# design.net
KiCad netlist of a schematic drawn in Altium Designer
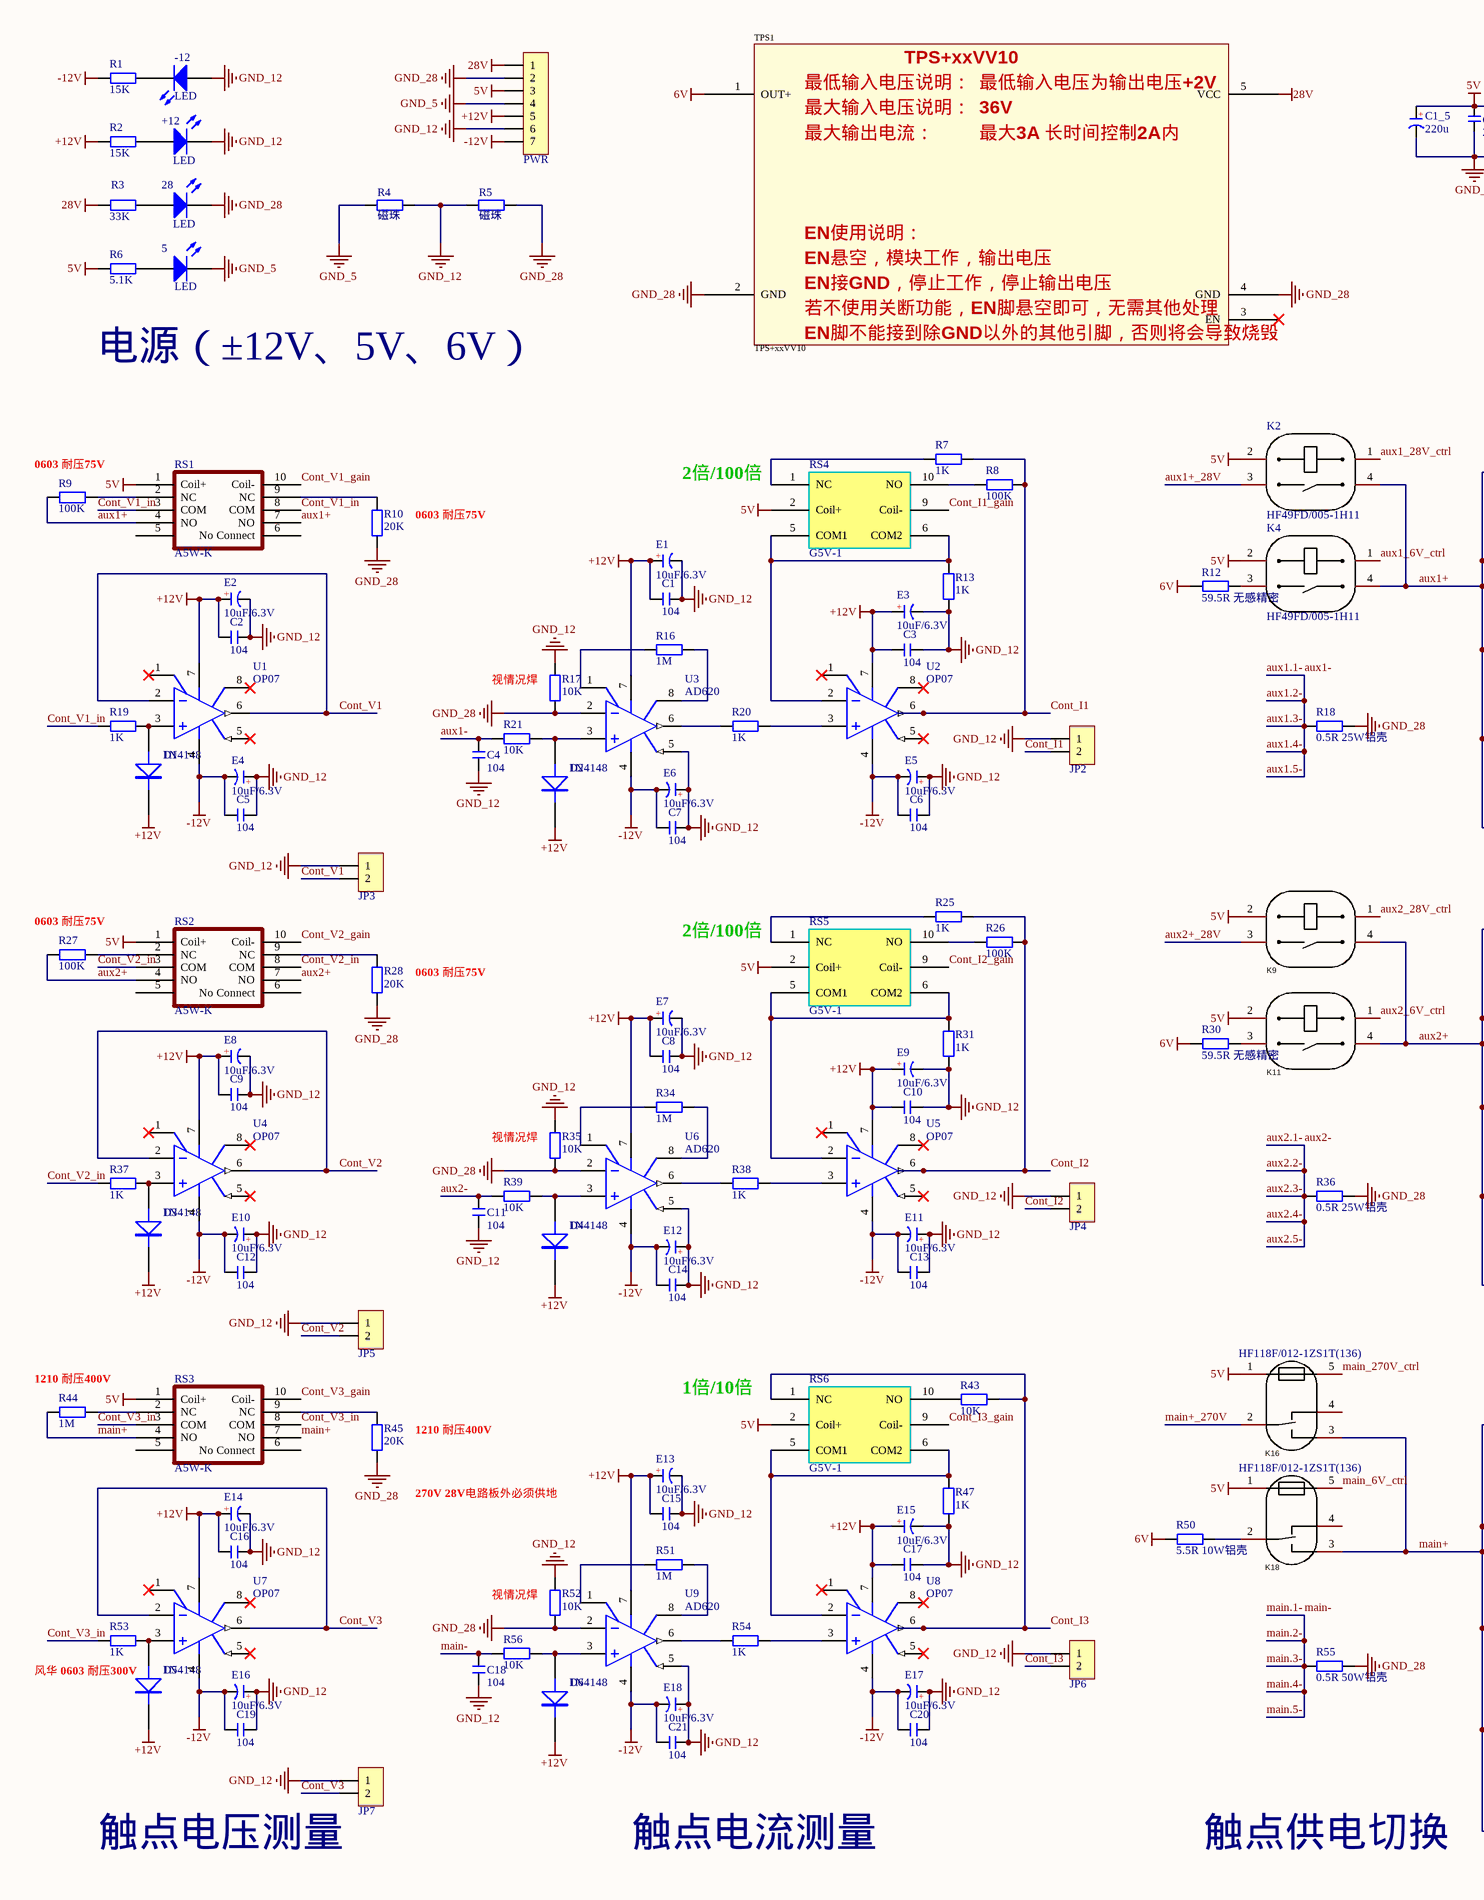
[diagram p0: 测试板.SchDoc, left]
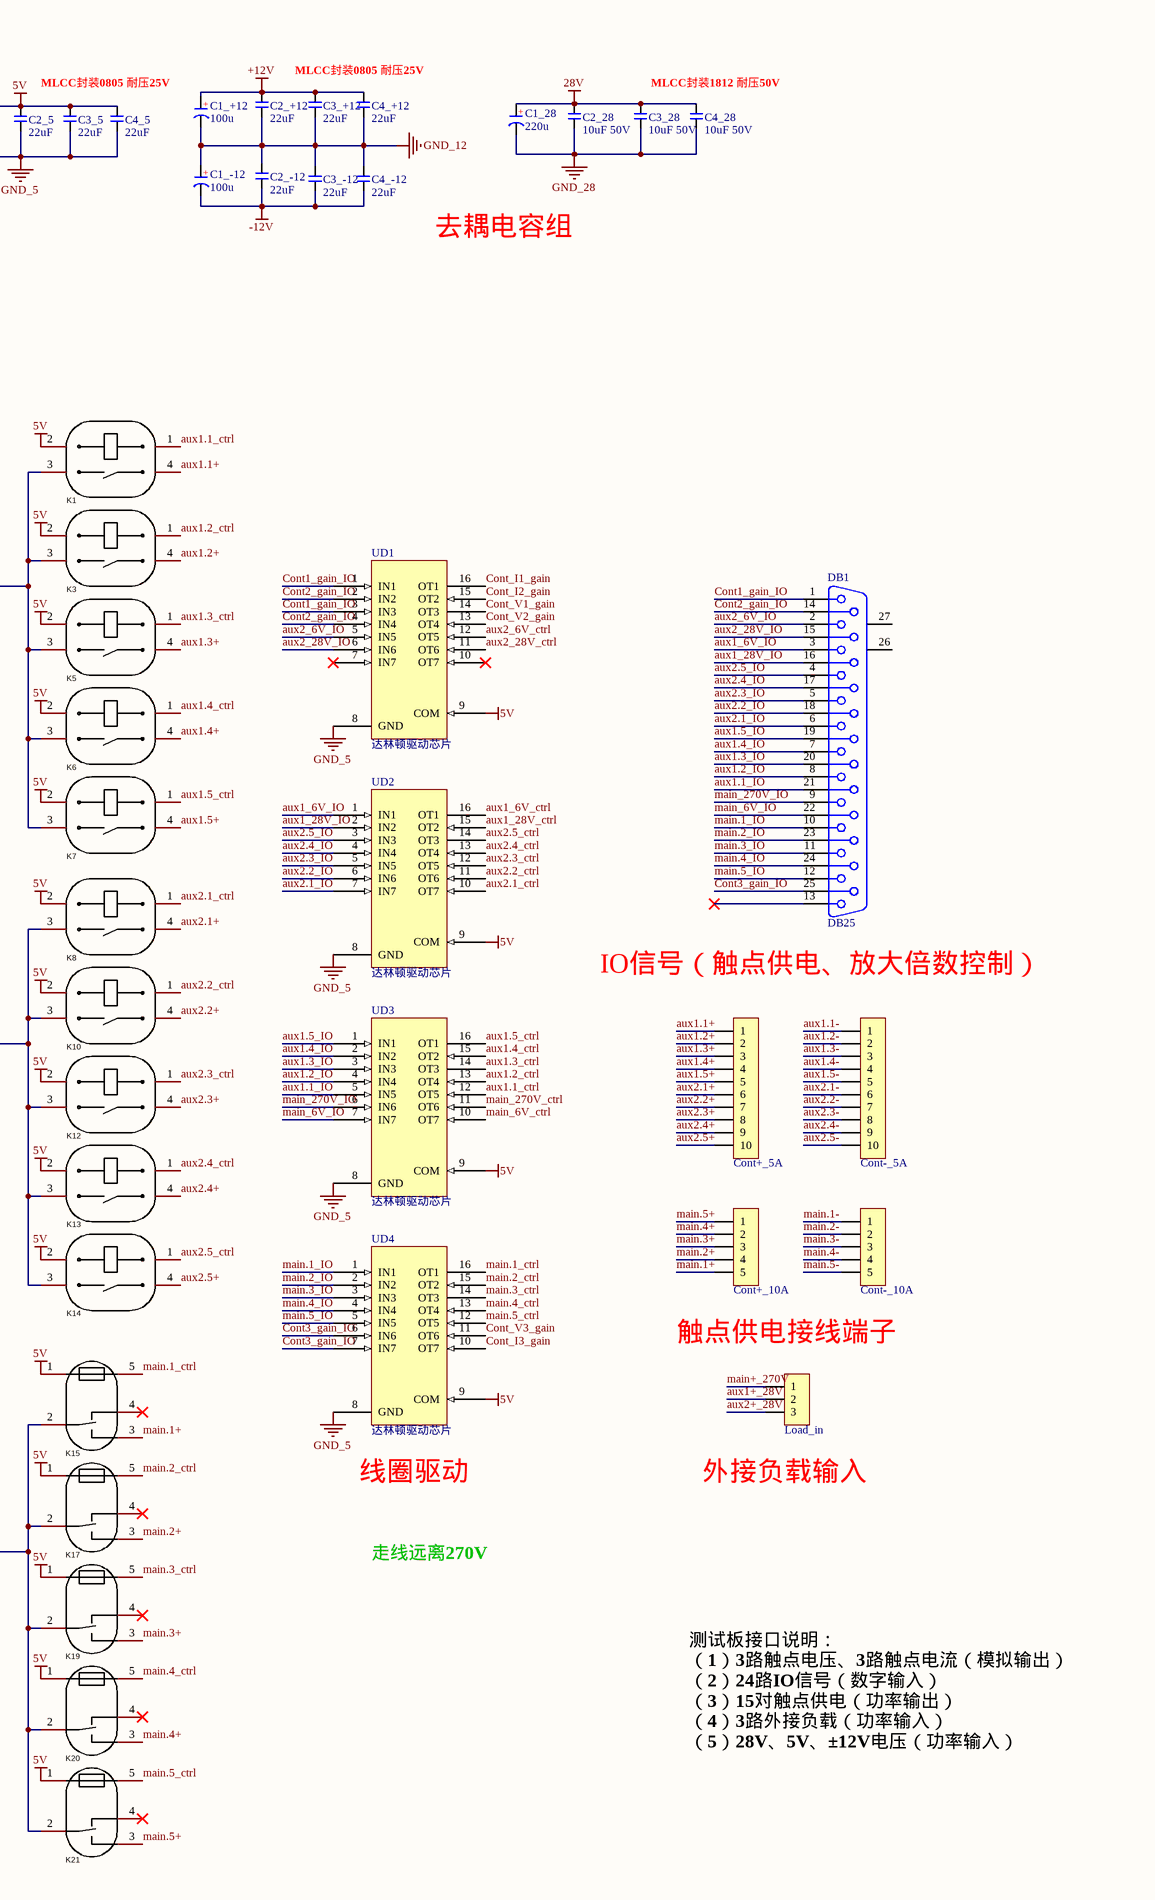
[diagram p1: 测试板.SchDoc, right]

(export (version "E")
  (design (tool "Eeschema 10.0.6"))
  (components
    (comp (ref "+12")
      (value "LED")
      (footprint "LED 0603B")
      (description "Typical BLUE SiC LED")
      (fields (field (name "PUBLISHER") "Altium Limited"))
      (libsource (lib "测控板") (part "LED3"))
    )
    (comp (ref "-12")
      (value "LED")
      (footprint "LED 0603B")
      (description "Typical BLUE SiC LED")
      (fields (field (name "PUBLISHER") "Altium Limited"))
      (libsource (lib "测控板") (part "LED3"))
    )
    (comp (ref "5")
      (value "LED")
      (footprint "LED 0603B")
      (description "Typical BLUE SiC LED")
      (fields (field (name "PUBLISHER") "Altium Limited"))
      (libsource (lib "测控板") (part "LED3"))
    )
    (comp (ref "28")
      (value "LED")
      (footprint "LED 0603B")
      (description "Typical BLUE SiC LED")
      (fields (field (name "PUBLISHER") "Altium Limited"))
      (libsource (lib "测控板") (part "LED3"))
    )
    (comp (ref "C1")
      (value "104")
      (footprint "C 0603_L")
      (description "贴片电容")
      (libsource (lib "0.1 - 电阻-电容-电感") (part "C"))
    )
    (comp (ref "C1_+12")
      (value "100u")
      (footprint "CAP 3.5*8*11.5")
      (description "Tantalum capacitor")
      (libsource (lib "SCHlibrary_of_ZYN") (part "T_CAP"))
    )
    (comp (ref "C1_-12")
      (value "100u")
      (footprint "CAP 3.5*8*11.5")
      (description "Tantalum capacitor")
      (libsource (lib "SCHlibrary_of_ZYN") (part "T_CAP"))
    )
    (comp (ref "C1_5")
      (value "220u")
      (footprint "CAP 3.5*8*11.5")
      (description "Tantalum capacitor")
      (libsource (lib "SCHlibrary_of_ZYN") (part "T_CAP"))
    )
    (comp (ref "C1_28")
      (value "220u")
      (footprint "CAP 3.5*8*11.5")
      (description "Tantalum capacitor")
      (libsource (lib "SCHlibrary_of_ZYN") (part "T_CAP"))
    )
    (comp (ref "C2")
      (value "104")
      (footprint "C 0603_L")
      (description "贴片电容")
      (libsource (lib "0.1 - 电阻-电容-电感") (part "C"))
    )
    (comp (ref "C2_+12")
      (value "xxuF/xxV/Footprint")
      (footprint "C 0805_L")
      (description "CAP MLCC")
      (fields (field (name "SCH NAME") "22uF"))
      (libsource (lib "Basal") (part "CAP MLCC"))
    )
    (comp (ref "C2_-12")
      (value "xxuF/xxV/Footprint")
      (footprint "C 0805_L")
      (description "CAP MLCC")
      (fields (field (name "SCH NAME") "22uF"))
      (libsource (lib "Basal") (part "CAP MLCC"))
    )
    (comp (ref "C2_5")
      (value "xxuF/xxV/Footprint")
      (footprint "C 0805_L")
      (description "CAP MLCC")
      (fields (field (name "SCH NAME") "22uF"))
      (libsource (lib "Basal") (part "CAP MLCC"))
    )
    (comp (ref "C2_28")
      (value "xxuF/xxV/Footprint")
      (footprint "C 1812_L")
      (description "CAP MLCC")
      (fields (field (name "SCH NAME") "10uF 50V"))
      (libsource (lib "Basal") (part "CAP MLCC"))
    )
    (comp (ref "C3")
      (value "104")
      (footprint "C 0603_L")
      (description "贴片电容")
      (libsource (lib "0.1 - 电阻-电容-电感") (part "C"))
    )
    (comp (ref "C3_+12")
      (value "xxuF/xxV/Footprint")
      (footprint "C 0805_L")
      (description "CAP MLCC")
      (fields (field (name "SCH NAME") "22uF"))
      (libsource (lib "Basal") (part "CAP MLCC"))
    )
    (comp (ref "C3_-12")
      (value "xxuF/xxV/Footprint")
      (footprint "C 0805_L")
      (description "CAP MLCC")
      (fields (field (name "SCH NAME") "22uF"))
      (libsource (lib "Basal") (part "CAP MLCC"))
    )
    (comp (ref "C3_5")
      (value "xxuF/xxV/Footprint")
      (footprint "C 0805_L")
      (description "CAP MLCC")
      (fields (field (name "SCH NAME") "22uF"))
      (libsource (lib "Basal") (part "CAP MLCC"))
    )
    (comp (ref "C3_28")
      (value "xxuF/xxV/Footprint")
      (footprint "C 1812_L")
      (description "CAP MLCC")
      (fields (field (name "SCH NAME") "10uF 50V"))
      (libsource (lib "Basal") (part "CAP MLCC"))
    )
    (comp (ref "C4")
      (value "104")
      (footprint "C 0603_L")
      (description "贴片电容")
      (libsource (lib "0.1 - 电阻-电容-电感") (part "C"))
    )
    (comp (ref "C4_+12")
      (value "xxuF/xxV/Footprint")
      (footprint "C 0805_L")
      (description "CAP MLCC")
      (fields (field (name "SCH NAME") "22uF"))
      (libsource (lib "Basal") (part "CAP MLCC"))
    )
    (comp (ref "C4_-12")
      (value "xxuF/xxV/Footprint")
      (footprint "C 0805_L")
      (description "CAP MLCC")
      (fields (field (name "SCH NAME") "22uF"))
      (libsource (lib "Basal") (part "CAP MLCC"))
    )
    (comp (ref "C4_5")
      (value "xxuF/xxV/Footprint")
      (footprint "C 0805_L")
      (description "CAP MLCC")
      (fields (field (name "SCH NAME") "22uF"))
      (libsource (lib "Basal") (part "CAP MLCC"))
    )
    (comp (ref "C4_28")
      (value "xxuF/xxV/Footprint")
      (footprint "C 1812_L")
      (description "CAP MLCC")
      (fields (field (name "SCH NAME") "10uF 50V"))
      (libsource (lib "Basal") (part "CAP MLCC"))
    )
    (comp (ref "C5")
      (value "104")
      (footprint "C 0603_L")
      (description "贴片电容")
      (libsource (lib "0.1 - 电阻-电容-电感") (part "C"))
    )
    (comp (ref "C6")
      (value "104")
      (footprint "C 0603_L")
      (description "贴片电容")
      (libsource (lib "0.1 - 电阻-电容-电感") (part "C"))
    )
    (comp (ref "C7")
      (value "104")
      (footprint "C 0603_L")
      (description "贴片电容")
      (libsource (lib "0.1 - 电阻-电容-电感") (part "C"))
    )
    (comp (ref "C8")
      (value "104")
      (footprint "C 0603_L")
      (description "贴片电容")
      (libsource (lib "0.1 - 电阻-电容-电感") (part "C"))
    )
    (comp (ref "C9")
      (value "104")
      (footprint "C 0603_L")
      (description "贴片电容")
      (libsource (lib "0.1 - 电阻-电容-电感") (part "C"))
    )
    (comp (ref "C10")
      (value "104")
      (footprint "C 0603_L")
      (description "贴片电容")
      (libsource (lib "0.1 - 电阻-电容-电感") (part "C"))
    )
    (comp (ref "C11")
      (value "104")
      (footprint "C 0603_L")
      (description "贴片电容")
      (libsource (lib "0.1 - 电阻-电容-电感") (part "C"))
    )
    (comp (ref "C12")
      (value "104")
      (footprint "C 0603_L")
      (description "贴片电容")
      (libsource (lib "0.1 - 电阻-电容-电感") (part "C"))
    )
    (comp (ref "C13")
      (value "104")
      (footprint "C 0603_L")
      (description "贴片电容")
      (libsource (lib "0.1 - 电阻-电容-电感") (part "C"))
    )
    (comp (ref "C14")
      (value "104")
      (footprint "C 0603_L")
      (description "贴片电容")
      (libsource (lib "0.1 - 电阻-电容-电感") (part "C"))
    )
    (comp (ref "C15")
      (value "104")
      (footprint "C 0603_L")
      (description "贴片电容")
      (libsource (lib "0.1 - 电阻-电容-电感") (part "C"))
    )
    (comp (ref "C16")
      (value "104")
      (footprint "C 0603_L")
      (description "贴片电容")
      (libsource (lib "0.1 - 电阻-电容-电感") (part "C"))
    )
    (comp (ref "C17")
      (value "104")
      (footprint "C 0603_L")
      (description "贴片电容")
      (libsource (lib "0.1 - 电阻-电容-电感") (part "C"))
    )
    (comp (ref "C18")
      (value "104")
      (footprint "C 0603_L")
      (description "贴片电容")
      (libsource (lib "0.1 - 电阻-电容-电感") (part "C"))
    )
    (comp (ref "C19")
      (value "104")
      (footprint "C 0603_L")
      (description "贴片电容")
      (libsource (lib "0.1 - 电阻-电容-电感") (part "C"))
    )
    (comp (ref "C20")
      (value "104")
      (footprint "C 0603_L")
      (description "贴片电容")
      (libsource (lib "0.1 - 电阻-电容-电感") (part "C"))
    )
    (comp (ref "C21")
      (value "104")
      (footprint "C 0603_L")
      (description "贴片电容")
      (libsource (lib "0.1 - 电阻-电容-电感") (part "C"))
    )
    (comp (ref "Cont+_5A")
      (value "HDR-1X10")
      (footprint "HT3.96-WI-10P")
      (description "10P接插件")
      (libsource (lib "5.4 - 接插件-脚距2.54 (100mil) ") (part "Header 10"))
    )
    (comp (ref "Cont+_10A")
      (value "HDR-1X5")
      (footprint "HT3.96-WI-5P")
      (description "5P接插件")
      (fields (field (name "版权归属") "封装库来自淘宝卖家 ID：黄晶宝石"))
      (libsource (lib "5.7 - 接插件-脚距3.96") (part "Header 5"))
    )
    (comp (ref "Cont-_5A")
      (value "HDR-1X10")
      (footprint "HT3.96-WI-10P")
      (description "10P接插件")
      (libsource (lib "5.4 - 接插件-脚距2.54 (100mil) ") (part "Header 10"))
    )
    (comp (ref "Cont-_10A")
      (value "HDR-1X5")
      (footprint "HT3.96-WI-5P")
      (description "5P接插件")
      (fields (field (name "版权归属") "封装库来自淘宝卖家 ID：黄晶宝石"))
      (libsource (lib "5.7 - 接插件-脚距3.96") (part "Header 5"))
    )
    (comp (ref "D1")
      (value "1N4148")
      (footprint "SOD-323")
      (description "Diode")
      (libsource (lib "测控板") (part "DIODE"))
    )
    (comp (ref "D2")
      (value "1N4148")
      (footprint "SOD-323")
      (description "Diode")
      (libsource (lib "测控板") (part "DIODE"))
    )
    (comp (ref "D3")
      (value "1N4148")
      (footprint "SOD-323")
      (description "Diode")
      (libsource (lib "测控板") (part "DIODE"))
    )
    (comp (ref "D4")
      (value "1N4148")
      (footprint "SOD-323")
      (description "Diode")
      (libsource (lib "测控板") (part "DIODE"))
    )
    (comp (ref "D5")
      (value "1N4148")
      (footprint "SOD-323")
      (description "Diode")
      (libsource (lib "测控板") (part "DIODE"))
    )
    (comp (ref "D6")
      (value "1N4148")
      (footprint "SOD-323")
      (description "Diode")
      (libsource (lib "测控板") (part "DIODE"))
    )
    (comp (ref "DB1")
      (value "DB25")
      (footprint "DB25")
      (description "Receptacle Assembly, 25 Position, Right Angle")
      (fields (field (name "PUBLISHER") "Altium Limited"))
      (libsource (lib "DDY library SCH") (part "D Connector 25"))
    )
    (comp (ref "E1")
      (value "10uF/6.3V")
      (footprint "CD B(3528)")
      (description "贴片钽电容")
      (libsource (lib "0.1 - 电阻-电容-电感") (part "CT"))
    )
    (comp (ref "E2")
      (value "10uF/6.3V")
      (footprint "CD B(3528)")
      (description "贴片钽电容")
      (libsource (lib "0.1 - 电阻-电容-电感") (part "CT"))
    )
    (comp (ref "E3")
      (value "10uF/6.3V")
      (footprint "CD B(3528)")
      (description "贴片钽电容")
      (libsource (lib "0.1 - 电阻-电容-电感") (part "CT"))
    )
    (comp (ref "E4")
      (value "10uF/6.3V")
      (footprint "CD B(3528)")
      (description "贴片钽电容")
      (libsource (lib "0.1 - 电阻-电容-电感") (part "CT"))
    )
    (comp (ref "E5")
      (value "10uF/6.3V")
      (footprint "CD B(3528)")
      (description "贴片钽电容")
      (libsource (lib "0.1 - 电阻-电容-电感") (part "CT"))
    )
    (comp (ref "E6")
      (value "10uF/6.3V")
      (footprint "CD B(3528)")
      (description "贴片钽电容")
      (libsource (lib "0.1 - 电阻-电容-电感") (part "CT"))
    )
    (comp (ref "E7")
      (value "10uF/6.3V")
      (footprint "CD B(3528)")
      (description "贴片钽电容")
      (libsource (lib "0.1 - 电阻-电容-电感") (part "CT"))
    )
    (comp (ref "E8")
      (value "10uF/6.3V")
      (footprint "CD B(3528)")
      (description "贴片钽电容")
      (libsource (lib "0.1 - 电阻-电容-电感") (part "CT"))
    )
    (comp (ref "E9")
      (value "10uF/6.3V")
      (footprint "CD B(3528)")
      (description "贴片钽电容")
      (libsource (lib "0.1 - 电阻-电容-电感") (part "CT"))
    )
    (comp (ref "E10")
      (value "10uF/6.3V")
      (footprint "CD B(3528)")
      (description "贴片钽电容")
      (libsource (lib "0.1 - 电阻-电容-电感") (part "CT"))
    )
    (comp (ref "E11")
      (value "10uF/6.3V")
      (footprint "CD B(3528)")
      (description "贴片钽电容")
      (libsource (lib "0.1 - 电阻-电容-电感") (part "CT"))
    )
    (comp (ref "E12")
      (value "10uF/6.3V")
      (footprint "CD B(3528)")
      (description "贴片钽电容")
      (libsource (lib "0.1 - 电阻-电容-电感") (part "CT"))
    )
    (comp (ref "E13")
      (value "10uF/6.3V")
      (footprint "CD B(3528)")
      (description "贴片钽电容")
      (libsource (lib "0.1 - 电阻-电容-电感") (part "CT"))
    )
    (comp (ref "E14")
      (value "10uF/6.3V")
      (footprint "CD B(3528)")
      (description "贴片钽电容")
      (libsource (lib "0.1 - 电阻-电容-电感") (part "CT"))
    )
    (comp (ref "E15")
      (value "10uF/6.3V")
      (footprint "CD B(3528)")
      (description "贴片钽电容")
      (libsource (lib "0.1 - 电阻-电容-电感") (part "CT"))
    )
    (comp (ref "E16")
      (value "10uF/6.3V")
      (footprint "CD B(3528)")
      (description "贴片钽电容")
      (libsource (lib "0.1 - 电阻-电容-电感") (part "CT"))
    )
    (comp (ref "E17")
      (value "10uF/6.3V")
      (footprint "CD B(3528)")
      (description "贴片钽电容")
      (libsource (lib "0.1 - 电阻-电容-电感") (part "CT"))
    )
    (comp (ref "E18")
      (value "10uF/6.3V")
      (footprint "CD B(3528)")
      (description "贴片钽电容")
      (libsource (lib "0.1 - 电阻-电容-电感") (part "CT"))
    )
    (comp (ref "JP2")
      (value "HDR-1X2")
      (footprint "KF2EDGK-2.54-WI-2P")
      (description "2P接插件")
      (fields (field (name "版权归属") "封装库来自淘宝 ID：黄晶宝石"))
      (libsource (lib "5.4 - 接插件-脚距2.54 (100mil) ") (part "Header 2"))
    )
    (comp (ref "JP3")
      (value "HDR-1X2")
      (footprint "KF2EDGK-2.54-WI-2P")
      (description "2P接插件")
      (fields (field (name "版权归属") "封装库来自淘宝 ID：黄晶宝石"))
      (libsource (lib "5.4 - 接插件-脚距2.54 (100mil) ") (part "Header 2"))
    )
    (comp (ref "JP4")
      (value "HDR-1X2")
      (footprint "KF2EDGK-2.54-WI-2P")
      (description "2P接插件")
      (fields (field (name "版权归属") "封装库来自淘宝 ID：黄晶宝石"))
      (libsource (lib "5.4 - 接插件-脚距2.54 (100mil) ") (part "Header 2"))
    )
    (comp (ref "JP5")
      (value "HDR-1X2")
      (footprint "KF2EDGK-2.54-WI-2P")
      (description "2P接插件")
      (fields (field (name "版权归属") "封装库来自淘宝 ID：黄晶宝石"))
      (libsource (lib "5.4 - 接插件-脚距2.54 (100mil) ") (part "Header 2"))
    )
    (comp (ref "JP6")
      (value "HDR-1X2")
      (footprint "KF2EDGK-2.54-WI-2P")
      (description "2P接插件")
      (fields (field (name "版权归属") "封装库来自淘宝 ID：黄晶宝石"))
      (libsource (lib "5.4 - 接插件-脚距2.54 (100mil) ") (part "Header 2"))
    )
    (comp (ref "JP7")
      (value "HDR-1X2")
      (footprint "KF2EDGK-2.54-WI-2P")
      (description "2P接插件")
      (fields (field (name "版权归属") "封装库来自淘宝 ID：黄晶宝石"))
      (libsource (lib "5.4 - 接插件-脚距2.54 (100mil) ") (part "Header 2"))
    )
    (comp (ref "K1")
      (value "HF49FD/005-1H11")
      (footprint "HF49FD-1H11")
      (fields (field (name "MANUFACTURER") "HF(宏发)"))
      (libsource (lib "HF49FD_005-1H11") (part "HF49FD/005-1H11"))
    )
    (comp (ref "K2")
      (value "HF49FD/005-1H11")
      (footprint "HF49FD-1H11")
      (fields (field (name "MANUFACTURER") "HF(宏发)"))
      (libsource (lib "HF49FD_005-1H11") (part "HF49FD/005-1H11"))
    )
    (comp (ref "K3")
      (value "HF49FD/005-1H11")
      (footprint "HF49FD-1H11")
      (fields (field (name "MANUFACTURER") "HF(宏发)"))
      (libsource (lib "HF49FD_005-1H11") (part "HF49FD/005-1H11"))
    )
    (comp (ref "K4")
      (value "HF49FD/005-1H11")
      (footprint "HF49FD-1H11")
      (fields (field (name "MANUFACTURER") "HF(宏发)"))
      (libsource (lib "HF49FD_005-1H11") (part "HF49FD/005-1H11"))
    )
    (comp (ref "K5")
      (value "HF49FD/005-1H11")
      (footprint "HF49FD-1H11")
      (fields (field (name "MANUFACTURER") "HF(宏发)"))
      (libsource (lib "HF49FD_005-1H11") (part "HF49FD/005-1H11"))
    )
    (comp (ref "K6")
      (value "HF49FD/005-1H11")
      (footprint "HF49FD-1H11")
      (fields (field (name "MANUFACTURER") "HF(宏发)"))
      (libsource (lib "HF49FD_005-1H11") (part "HF49FD/005-1H11"))
    )
    (comp (ref "K7")
      (value "HF49FD/005-1H11")
      (footprint "HF49FD-1H11")
      (fields (field (name "MANUFACTURER") "HF(宏发)"))
      (libsource (lib "HF49FD_005-1H11") (part "HF49FD/005-1H11"))
    )
    (comp (ref "K8")
      (value "HF49FD/005-1H11")
      (footprint "HF49FD-1H11")
      (fields (field (name "MANUFACTURER") "HF(宏发)"))
      (libsource (lib "HF49FD_005-1H11") (part "HF49FD/005-1H11"))
    )
    (comp (ref "K9")
      (value "HF49FD/005-1H11")
      (footprint "HF49FD-1H11")
      (fields (field (name "MANUFACTURER") "HF(宏发)"))
      (libsource (lib "HF49FD_005-1H11") (part "HF49FD/005-1H11"))
    )
    (comp (ref "K10")
      (value "HF49FD/005-1H11")
      (footprint "HF49FD-1H11")
      (fields (field (name "MANUFACTURER") "HF(宏发)"))
      (libsource (lib "HF49FD_005-1H11") (part "HF49FD/005-1H11"))
    )
    (comp (ref "K11")
      (value "HF49FD/005-1H11")
      (footprint "HF49FD-1H11")
      (fields (field (name "MANUFACTURER") "HF(宏发)"))
      (libsource (lib "HF49FD_005-1H11") (part "HF49FD/005-1H11"))
    )
    (comp (ref "K12")
      (value "HF49FD/005-1H11")
      (footprint "HF49FD-1H11")
      (fields (field (name "MANUFACTURER") "HF(宏发)"))
      (libsource (lib "HF49FD_005-1H11") (part "HF49FD/005-1H11"))
    )
    (comp (ref "K13")
      (value "HF49FD/005-1H11")
      (footprint "HF49FD-1H11")
      (fields (field (name "MANUFACTURER") "HF(宏发)"))
      (libsource (lib "HF49FD_005-1H11") (part "HF49FD/005-1H11"))
    )
    (comp (ref "K14")
      (value "HF49FD/005-1H11")
      (footprint "HF49FD-1H11")
      (fields (field (name "MANUFACTURER") "HF(宏发)"))
      (libsource (lib "HF49FD_005-1H11") (part "HF49FD/005-1H11"))
    )
    (comp (ref "K15")
      (value "HF118F/012-1ZS1T(136)")
      (footprint "RELAY-TH_HF118F-X-1ZX1X-XXX")
      (fields (field (name "MANUFACTURER") "HF(宏发)"))
      (libsource (lib "HF118F_012-1ZS1T") (part "HF118F/012-1ZS1T(136)"))
    )
    (comp (ref "K16")
      (value "HF118F/012-1ZS1T(136)")
      (footprint "RELAY-TH_HF118F-X-1ZX1X-XXX")
      (fields (field (name "MANUFACTURER") "HF(宏发)"))
      (libsource (lib "HF118F_012-1ZS1T") (part "HF118F/012-1ZS1T(136)"))
    )
    (comp (ref "K17")
      (value "HF118F/012-1ZS1T(136)")
      (footprint "RELAY-TH_HF118F-X-1ZX1X-XXX")
      (fields (field (name "MANUFACTURER") "HF(宏发)"))
      (libsource (lib "HF118F_012-1ZS1T") (part "HF118F/012-1ZS1T(136)"))
    )
    (comp (ref "K18")
      (value "HF118F/012-1ZS1T(136)")
      (footprint "RELAY-TH_HF118F-X-1ZX1X-XXX")
      (fields (field (name "MANUFACTURER") "HF(宏发)"))
      (libsource (lib "HF118F_012-1ZS1T") (part "HF118F/012-1ZS1T(136)"))
    )
    (comp (ref "K19")
      (value "HF118F/012-1ZS1T(136)")
      (footprint "RELAY-TH_HF118F-X-1ZX1X-XXX")
      (fields (field (name "MANUFACTURER") "HF(宏发)"))
      (libsource (lib "HF118F_012-1ZS1T") (part "HF118F/012-1ZS1T(136)"))
    )
    (comp (ref "K20")
      (value "HF118F/012-1ZS1T(136)")
      (footprint "RELAY-TH_HF118F-X-1ZX1X-XXX")
      (fields (field (name "MANUFACTURER") "HF(宏发)"))
      (libsource (lib "HF118F_012-1ZS1T") (part "HF118F/012-1ZS1T(136)"))
    )
    (comp (ref "K21")
      (value "HF118F/012-1ZS1T(136)")
      (footprint "RELAY-TH_HF118F-X-1ZX1X-XXX")
      (fields (field (name "MANUFACTURER") "HF(宏发)"))
      (libsource (lib "HF118F_012-1ZS1T") (part "HF118F/012-1ZS1T(136)"))
    )
    (comp (ref "Load_in")
      (value "HDR-1X3")
      (footprint "HT3.96-WI-3P")
      (description "3P接插件")
      (fields (field (name "版权归属") "封装库来自淘宝卖家 ID：黄晶宝石"))
      (libsource (lib "5.7 - 接插件-脚距3.96") (part "Header 3"))
    )
    (comp (ref "PWR")
      (value "HDR-1X7")
      (footprint "HT3.96-WI-7P")
      (description "7P接插件")
      (fields (field (name "版权归属") "封装库来自淘宝卖家 ID：黄晶宝石"))
      (libsource (lib "6.1 - 接插件-脚距5.08 (200mil) ") (part "Header 7"))
    )
    (comp (ref "R1")
      (value "15K")
      (footprint "R 0603_L")
      (description "贴片电阻")
      (fields (field (name "版权归属") "来自淘宝 ID：黄晶宝石"))
      (libsource (lib "0.1 - 电阻-电容-电感") (part "R"))
    )
    (comp (ref "R2")
      (value "15K")
      (footprint "R 0603_L")
      (description "贴片电阻")
      (fields (field (name "版权归属") "来自淘宝 ID：黄晶宝石"))
      (libsource (lib "0.1 - 电阻-电容-电感") (part "R"))
    )
    (comp (ref "R3")
      (value "33K")
      (footprint "R 0603_L")
      (description "贴片电阻")
      (fields (field (name "版权归属") "来自淘宝 ID：黄晶宝石"))
      (libsource (lib "0.1 - 电阻-电容-电感") (part "R"))
    )
    (comp (ref "R4")
      (value "磁珠")
      (footprint "AXIAL0.4-1/4W")
      (description "Resistor")
      (fields (field (name "PUBLISHER") "Altium Limited"))
      (libsource (lib "Miscellaneous Devices") (part "Res2"))
    )
    (comp (ref "R5")
      (value "磁珠")
      (footprint "AXIAL0.4-1/4W")
      (description "Resistor")
      (fields (field (name "PUBLISHER") "Altium Limited"))
      (libsource (lib "Miscellaneous Devices") (part "Res2"))
    )
    (comp (ref "R6")
      (value "5.1K")
      (footprint "R 0603_L")
      (description "贴片电阻")
      (fields (field (name "版权归属") "来自淘宝 ID：黄晶宝石"))
      (libsource (lib "0.1 - 电阻-电容-电感") (part "R"))
    )
    (comp (ref "R7")
      (value "1K")
      (footprint "R 0603_L")
      (description "贴片电阻")
      (fields (field (name "版权归属") "来自淘宝 ID：黄晶宝石"))
      (libsource (lib "0.1 - 电阻-电容-电感") (part "R"))
    )
    (comp (ref "R8")
      (value "100K")
      (footprint "R 0603_L")
      (description "贴片电阻")
      (fields (field (name "版权归属") "来自淘宝 ID：黄晶宝石"))
      (libsource (lib "0.1 - 电阻-电容-电感") (part "R"))
    )
    (comp (ref "R9")
      (value "100K")
      (footprint "R 0603_L")
      (description "贴片电阻")
      (fields (field (name "版权归属") "来自淘宝 ID：黄晶宝石"))
      (libsource (lib "0.1 - 电阻-电容-电感") (part "R"))
    )
    (comp (ref "R10")
      (value "20K")
      (footprint "R 0603_L")
      (description "贴片电阻")
      (fields (field (name "版权归属") "来自淘宝 ID：黄晶宝石"))
      (libsource (lib "0.1 - 电阻-电容-电感") (part "R"))
    )
    (comp (ref "R12")
      (value "59.5R 无感精密")
      (footprint "无感精密电阻3W")
      (description "贴片电阻")
      (fields (field (name "版权归属") "来自淘宝 ID：黄晶宝石"))
      (libsource (lib "0.1 - 电阻-电容-电感") (part "R"))
    )
    (comp (ref "R13")
      (value "1K")
      (footprint "R 0603_L")
      (description "贴片电阻")
      (fields (field (name "版权归属") "来自淘宝 ID：黄晶宝石"))
      (libsource (lib "0.1 - 电阻-电容-电感") (part "R"))
    )
    (comp (ref "R16")
      (value "1M")
      (footprint "R 0603_L")
      (description "贴片电阻")
      (fields (field (name "版权归属") "来自淘宝 ID：黄晶宝石"))
      (libsource (lib "0.1 - 电阻-电容-电感") (part "R"))
    )
    (comp (ref "R17")
      (value "10K")
      (footprint "R 0603_L")
      (description "贴片电阻")
      (fields (field (name "版权归属") "来自淘宝 ID：黄晶宝石"))
      (libsource (lib "0.1 - 电阻-电容-电感") (part "R"))
    )
    (comp (ref "R18")
      (value "0.5R 25W铝壳")
      (footprint "黄金铝壳1R25W")
      (description "贴片电阻")
      (fields (field (name "版权归属") "来自淘宝 ID：黄晶宝石"))
      (libsource (lib "0.1 - 电阻-电容-电感") (part "R"))
    )
    (comp (ref "R19")
      (value "1K")
      (footprint "R 0603_L")
      (description "贴片电阻")
      (fields (field (name "版权归属") "来自淘宝 ID：黄晶宝石"))
      (libsource (lib "0.1 - 电阻-电容-电感") (part "R"))
    )
    (comp (ref "R20")
      (value "1K")
      (footprint "R 0603_L")
      (description "贴片电阻")
      (fields (field (name "版权归属") "来自淘宝 ID：黄晶宝石"))
      (libsource (lib "0.1 - 电阻-电容-电感") (part "R"))
    )
    (comp (ref "R21")
      (value "10K")
      (footprint "R 0603_L")
      (description "贴片电阻")
      (fields (field (name "版权归属") "来自淘宝 ID：黄晶宝石"))
      (libsource (lib "0.1 - 电阻-电容-电感") (part "R"))
    )
    (comp (ref "R25")
      (value "1K")
      (footprint "R 0603_L")
      (description "贴片电阻")
      (fields (field (name "版权归属") "来自淘宝 ID：黄晶宝石"))
      (libsource (lib "0.1 - 电阻-电容-电感") (part "R"))
    )
    (comp (ref "R26")
      (value "100K")
      (footprint "R 0603_L")
      (description "贴片电阻")
      (fields (field (name "版权归属") "来自淘宝 ID：黄晶宝石"))
      (libsource (lib "0.1 - 电阻-电容-电感") (part "R"))
    )
    (comp (ref "R27")
      (value "100K")
      (footprint "R 0603_L")
      (description "贴片电阻")
      (fields (field (name "版权归属") "来自淘宝 ID：黄晶宝石"))
      (libsource (lib "0.1 - 电阻-电容-电感") (part "R"))
    )
    (comp (ref "R28")
      (value "20K")
      (footprint "R 0603_L")
      (description "贴片电阻")
      (fields (field (name "版权归属") "来自淘宝 ID：黄晶宝石"))
      (libsource (lib "0.1 - 电阻-电容-电感") (part "R"))
    )
    (comp (ref "R30")
      (value "59.5R 无感精密")
      (footprint "无感精密电阻3W")
      (description "贴片电阻")
      (fields (field (name "版权归属") "来自淘宝 ID：黄晶宝石"))
      (libsource (lib "0.1 - 电阻-电容-电感") (part "R"))
    )
    (comp (ref "R31")
      (value "1K")
      (footprint "R 0603_L")
      (description "贴片电阻")
      (fields (field (name "版权归属") "来自淘宝 ID：黄晶宝石"))
      (libsource (lib "0.1 - 电阻-电容-电感") (part "R"))
    )
    (comp (ref "R34")
      (value "1M")
      (footprint "R 0603_L")
      (description "贴片电阻")
      (fields (field (name "版权归属") "来自淘宝 ID：黄晶宝石"))
      (libsource (lib "0.1 - 电阻-电容-电感") (part "R"))
    )
    (comp (ref "R35")
      (value "10K")
      (footprint "R 0603_L")
      (description "贴片电阻")
      (fields (field (name "版权归属") "来自淘宝 ID：黄晶宝石"))
      (libsource (lib "0.1 - 电阻-电容-电感") (part "R"))
    )
    (comp (ref "R36")
      (value "0.5R 25W铝壳")
      (footprint "黄金铝壳1R25W")
      (description "贴片电阻")
      (fields (field (name "版权归属") "来自淘宝 ID：黄晶宝石"))
      (libsource (lib "0.1 - 电阻-电容-电感") (part "R"))
    )
    (comp (ref "R37")
      (value "1K")
      (footprint "R 0603_L")
      (description "贴片电阻")
      (fields (field (name "版权归属") "来自淘宝 ID：黄晶宝石"))
      (libsource (lib "0.1 - 电阻-电容-电感") (part "R"))
    )
    (comp (ref "R38")
      (value "1K")
      (footprint "R 0603_L")
      (description "贴片电阻")
      (fields (field (name "版权归属") "来自淘宝 ID：黄晶宝石"))
      (libsource (lib "0.1 - 电阻-电容-电感") (part "R"))
    )
    (comp (ref "R39")
      (value "10K")
      (footprint "R 0603_L")
      (description "贴片电阻")
      (fields (field (name "版权归属") "来自淘宝 ID：黄晶宝石"))
      (libsource (lib "0.1 - 电阻-电容-电感") (part "R"))
    )
    (comp (ref "R43")
      (value "10K")
      (footprint "R 0603_L")
      (description "贴片电阻")
      (fields (field (name "版权归属") "来自淘宝 ID：黄晶宝石"))
      (libsource (lib "0.1 - 电阻-电容-电感") (part "R"))
    )
    (comp (ref "R44")
      (value "1M")
      (footprint "R 2010_L")
      (description "贴片电阻")
      (fields (field (name "版权归属") "来自淘宝 ID：黄晶宝石"))
      (libsource (lib "0.1 - 电阻-电容-电感") (part "R"))
    )
    (comp (ref "R45")
      (value "20K")
      (footprint "R 2010_L")
      (description "贴片电阻")
      (fields (field (name "版权归属") "来自淘宝 ID：黄晶宝石"))
      (libsource (lib "0.1 - 电阻-电容-电感") (part "R"))
    )
    (comp (ref "R47")
      (value "1K")
      (footprint "R 0603_L")
      (description "贴片电阻")
      (fields (field (name "版权归属") "来自淘宝 ID：黄晶宝石"))
      (libsource (lib "0.1 - 电阻-电容-电感") (part "R"))
    )
    (comp (ref "R50")
      (value "5.5R 10W铝壳")
      (footprint "RX24-10W")
      (description "贴片电阻")
      (fields (field (name "版权归属") "来自淘宝 ID：黄晶宝石"))
      (libsource (lib "0.1 - 电阻-电容-电感") (part "R"))
    )
    (comp (ref "R51")
      (value "1M")
      (footprint "R 0603_L")
      (description "贴片电阻")
      (fields (field (name "版权归属") "来自淘宝 ID：黄晶宝石"))
      (libsource (lib "0.1 - 电阻-电容-电感") (part "R"))
    )
    (comp (ref "R52")
      (value "10K")
      (footprint "R 0603_L")
      (description "贴片电阻")
      (fields (field (name "版权归属") "来自淘宝 ID：黄晶宝石"))
      (libsource (lib "0.1 - 电阻-电容-电感") (part "R"))
    )
    (comp (ref "R53")
      (value "1K")
      (footprint "R 0603_L")
      (description "贴片电阻")
      (fields (field (name "版权归属") "来自淘宝 ID：黄晶宝石"))
      (libsource (lib "0.1 - 电阻-电容-电感") (part "R"))
    )
    (comp (ref "R54")
      (value "1K")
      (footprint "R 0603_L")
      (description "贴片电阻")
      (fields (field (name "版权归属") "来自淘宝 ID：黄晶宝石"))
      (libsource (lib "0.1 - 电阻-电容-电感") (part "R"))
    )
    (comp (ref "R55")
      (value "0.5R 50W铝壳")
      (footprint "黄金铝壳0.5R50W")
      (description "贴片电阻")
      (fields (field (name "版权归属") "来自淘宝 ID：黄晶宝石"))
      (libsource (lib "0.1 - 电阻-电容-电感") (part "R"))
    )
    (comp (ref "R56")
      (value "10K")
      (footprint "R 0603_L")
      (description "贴片电阻")
      (fields (field (name "版权归属") "来自淘宝 ID：黄晶宝石"))
      (libsource (lib "0.1 - 电阻-电容-电感") (part "R"))
    )
    (comp (ref "RS1") (value "A5W-K") (footprint "NewA5W_K") (libsource (lib "测控板") (part "Relay")))
    (comp (ref "RS2") (value "A5W-K") (footprint "NewA5W_K") (libsource (lib "测控板") (part "Relay")))
    (comp (ref "RS3") (value "A5W-K") (footprint "NewA5W_K") (libsource (lib "测控板") (part "Relay")))
    (comp (ref "RS4") (value "G5V-1") (footprint "G5V-1") (libsource (lib "G5V-1") (part "G5V-1")))
    (comp (ref "RS5") (value "G5V-1") (footprint "G5V-1") (libsource (lib "G5V-1") (part "G5V-1")))
    (comp (ref "RS6") (value "G5V-1") (footprint "G5V-1") (libsource (lib "G5V-1") (part "G5V-1")))
    (comp (ref "TPS1")
      (value "TPS+xxVV10")
      (footprint "TPS+xxVV10模块贴片封装")
      (libsource (lib "【TPS+xxVV10】模块封装资料") (part "TPS+xxVV10"))
    )
    (comp (ref "U1")
      (value "OP07")
      (footprint "SOP8")
      (description "Precision Instrumentation Amplifier")
      (libsource (lib "测控板") (part "AD620AR (8)"))
    )
    (comp (ref "U2")
      (value "OP07")
      (footprint "SOP8")
      (description "Precision Instrumentation Amplifier")
      (libsource (lib "测控板") (part "AD620AR (8)"))
    )
    (comp (ref "U3")
      (value "AD620")
      (footprint "SOP8")
      (description "Precision Instrumentation Amplifier")
      (libsource (lib "测控板") (part "AD620AR (8)"))
    )
    (comp (ref "U4")
      (value "OP07")
      (footprint "SOP8")
      (description "Precision Instrumentation Amplifier")
      (libsource (lib "测控板") (part "AD620AR (8)"))
    )
    (comp (ref "U5")
      (value "OP07")
      (footprint "SOP8")
      (description "Precision Instrumentation Amplifier")
      (libsource (lib "测控板") (part "AD620AR (8)"))
    )
    (comp (ref "U6")
      (value "AD620")
      (footprint "SOP8")
      (description "Precision Instrumentation Amplifier")
      (libsource (lib "测控板") (part "AD620AR (8)"))
    )
    (comp (ref "U7")
      (value "OP07")
      (footprint "SOP8")
      (description "Precision Instrumentation Amplifier")
      (libsource (lib "测控板") (part "AD620AR (8)"))
    )
    (comp (ref "U8")
      (value "OP07")
      (footprint "SOP8")
      (description "Precision Instrumentation Amplifier")
      (libsource (lib "测控板") (part "AD620AR (8)"))
    )
    (comp (ref "U9")
      (value "AD620")
      (footprint "SOP8")
      (description "Precision Instrumentation Amplifier")
      (libsource (lib "测控板") (part "AD620AR (8)"))
    )
    (comp (ref "UD1") (value "达林顿驱动芯片") (footprint "SOP16") (libsource (lib "1.0 - 常见芯片") (part "ULN2003")))
    (comp (ref "UD2") (value "达林顿驱动芯片") (footprint "SOP16") (libsource (lib "1.0 - 常见芯片") (part "ULN2003")))
    (comp (ref "UD3") (value "达林顿驱动芯片") (footprint "SOP16") (libsource (lib "1.0 - 常见芯片") (part "ULN2003")))
    (comp (ref "UD4") (value "达林顿驱动芯片") (footprint "SOP16") (libsource (lib "1.0 - 常见芯片") (part "ULN2003")))
  )
  (nets
    (net (code "1") (name "+12V") (class "Default")
      (node (ref "C1") (pin "1") (pinfunction "1_1") (pintype "passive"))
      (node (ref "C10") (pin "1") (pinfunction "1_1") (pintype "passive"))
      (node (ref "C15") (pin "1") (pinfunction "1_1") (pintype "passive"))
      (node (ref "C16") (pin "1") (pinfunction "1_1") (pintype "passive"))
      (node (ref "C17") (pin "1") (pinfunction "1_1") (pintype "passive"))
      (node (ref "C1_+12") (pin "1") (pinfunction "A_1") (pintype "passive"))
      (node (ref "C2") (pin "1") (pinfunction "1_1") (pintype "passive"))
      (node (ref "C2_+12") (pin "1") (pintype "passive"))
      (node (ref "C3") (pin "1") (pinfunction "1_1") (pintype "passive"))
      (node (ref "C3_+12") (pin "1") (pintype "passive"))
      (node (ref "C4_+12") (pin "1") (pintype "passive"))
      (node (ref "C8") (pin "1") (pinfunction "1_1") (pintype "passive"))
      (node (ref "C9") (pin "1") (pinfunction "1_1") (pintype "passive"))
      (node (ref "D1") (pin "2") (pinfunction "K_2") (pintype "passive"))
      (node (ref "D2") (pin "2") (pinfunction "K_2") (pintype "passive"))
      (node (ref "D3") (pin "2") (pinfunction "K_2") (pintype "passive"))
      (node (ref "D4") (pin "2") (pinfunction "K_2") (pintype "passive"))
      (node (ref "D5") (pin "2") (pinfunction "K_2") (pintype "passive"))
      (node (ref "D6") (pin "2") (pinfunction "K_2") (pintype "passive"))
      (node (ref "E1") (pin "1") (pinfunction "A_1") (pintype "passive"))
      (node (ref "E13") (pin "1") (pinfunction "A_1") (pintype "passive"))
      (node (ref "E14") (pin "1") (pinfunction "A_1") (pintype "passive"))
      (node (ref "E15") (pin "1") (pinfunction "A_1") (pintype "passive"))
      (node (ref "E2") (pin "1") (pinfunction "A_1") (pintype "passive"))
      (node (ref "E3") (pin "1") (pinfunction "A_1") (pintype "passive"))
      (node (ref "E7") (pin "1") (pinfunction "A_1") (pintype "passive"))
      (node (ref "E8") (pin "1") (pinfunction "A_1") (pintype "passive"))
      (node (ref "E9") (pin "1") (pinfunction "A_1") (pintype "passive"))
      (node (ref "PWR") (pin "5") (pinfunction "5_5") (pintype "passive"))
      (node (ref "R2") (pin "2") (pinfunction "2_2") (pintype "passive"))
      (node (ref "U1") (pin "7") (pinfunction "V+_7") (pintype "power_in"))
      (node (ref "U2") (pin "7") (pinfunction "V+_7") (pintype "power_in"))
      (node (ref "U3") (pin "7") (pinfunction "V+_7") (pintype "power_in"))
      (node (ref "U4") (pin "7") (pinfunction "V+_7") (pintype "power_in"))
      (node (ref "U5") (pin "7") (pinfunction "V+_7") (pintype "power_in"))
      (node (ref "U6") (pin "7") (pinfunction "V+_7") (pintype "power_in"))
      (node (ref "U7") (pin "7") (pinfunction "V+_7") (pintype "power_in"))
      (node (ref "U8") (pin "7") (pinfunction "V+_7") (pintype "power_in"))
      (node (ref "U9") (pin "7") (pinfunction "V+_7") (pintype "power_in"))
    )
    (net (code "2") (name "-12V") (class "Default")
      (node (ref "C12") (pin "1") (pinfunction "1_1") (pintype "passive"))
      (node (ref "C13") (pin "1") (pinfunction "1_1") (pintype "passive"))
      (node (ref "C14") (pin "1") (pinfunction "1_1") (pintype "passive"))
      (node (ref "C19") (pin "1") (pinfunction "1_1") (pintype "passive"))
      (node (ref "C1_-12") (pin "2") (pinfunction "K_2") (pintype "passive"))
      (node (ref "C20") (pin "1") (pinfunction "1_1") (pintype "passive"))
      (node (ref "C21") (pin "1") (pinfunction "1_1") (pintype "passive"))
      (node (ref "C2_-12") (pin "2") (pintype "passive"))
      (node (ref "C3_-12") (pin "2") (pintype "passive"))
      (node (ref "C4_-12") (pin "2") (pintype "passive"))
      (node (ref "C5") (pin "1") (pinfunction "1_1") (pintype "passive"))
      (node (ref "C6") (pin "1") (pinfunction "1_1") (pintype "passive"))
      (node (ref "C7") (pin "1") (pinfunction "1_1") (pintype "passive"))
      (node (ref "E10") (pin "2") (pinfunction "K_2") (pintype "passive"))
      (node (ref "E11") (pin "2") (pinfunction "K_2") (pintype "passive"))
      (node (ref "E12") (pin "2") (pinfunction "K_2") (pintype "passive"))
      (node (ref "E16") (pin "2") (pinfunction "K_2") (pintype "passive"))
      (node (ref "E17") (pin "2") (pinfunction "K_2") (pintype "passive"))
      (node (ref "E18") (pin "2") (pinfunction "K_2") (pintype "passive"))
      (node (ref "E4") (pin "2") (pinfunction "K_2") (pintype "passive"))
      (node (ref "E5") (pin "2") (pinfunction "K_2") (pintype "passive"))
      (node (ref "E6") (pin "2") (pinfunction "K_2") (pintype "passive"))
      (node (ref "PWR") (pin "7") (pinfunction "7_7") (pintype "passive"))
      (node (ref "R1") (pin "2") (pinfunction "2_2") (pintype "passive"))
      (node (ref "U1") (pin "4") (pinfunction "V-_4") (pintype "power_in"))
      (node (ref "U2") (pin "4") (pinfunction "V-_4") (pintype "power_in"))
      (node (ref "U3") (pin "4") (pinfunction "V-_4") (pintype "power_in"))
      (node (ref "U4") (pin "4") (pinfunction "V-_4") (pintype "power_in"))
      (node (ref "U5") (pin "4") (pinfunction "V-_4") (pintype "power_in"))
      (node (ref "U6") (pin "4") (pinfunction "V-_4") (pintype "power_in"))
      (node (ref "U7") (pin "4") (pinfunction "V-_4") (pintype "power_in"))
      (node (ref "U8") (pin "4") (pinfunction "V-_4") (pintype "power_in"))
      (node (ref "U9") (pin "4") (pinfunction "V-_4") (pintype "power_in"))
    )
    (net (code "3") (name "/Cont1_gain_IO") (class "Default")
      (node (ref "DB1") (pin "1") (pinfunction "1_1") (pintype "passive"))
      (node (ref "UD1") (pin "1") (pinfunction "IN1_1") (pintype "input"))
      (node (ref "UD1") (pin "3") (pinfunction "IN3_3") (pintype "input"))
    )
    (net (code "4") (name "/Cont2_gain_IO") (class "Default")
      (node (ref "DB1") (pin "14") (pinfunction "14_14") (pintype "passive"))
      (node (ref "UD1") (pin "2") (pinfunction "IN2_2") (pintype "input"))
      (node (ref "UD1") (pin "4") (pinfunction "IN4_4") (pintype "input"))
    )
    (net (code "5") (name "/Cont3_gain_IO") (class "Default")
      (node (ref "DB1") (pin "25") (pinfunction "25_25") (pintype "passive"))
      (node (ref "UD4") (pin "6") (pinfunction "IN6_6") (pintype "input"))
      (node (ref "UD4") (pin "7") (pinfunction "IN7_7") (pintype "input"))
    )
    (net (code "6") (name "/Cont_I1") (class "Default")
      (node (ref "JP2") (pin "2") (pinfunction "2_2") (pintype "passive"))
      (node (ref "R7") (pin "1") (pinfunction "1_1") (pintype "passive"))
      (node (ref "R8") (pin "1") (pinfunction "1_1") (pintype "passive"))
      (node (ref "U2") (pin "6") (pinfunction "OUT_6") (pintype "output"))
    )
    (net (code "7") (name "/Cont_I1_gain") (class "Default")
      (node (ref "RS4") (pin "9") (pinfunction "Coil-_9") (pintype "passive"))
      (node (ref "UD1") (pin "16") (pinfunction "OT1_16") (pintype "power_in"))
    )
    (net (code "8") (name "/Cont_I2") (class "Default")
      (node (ref "JP4") (pin "2") (pinfunction "2_2") (pintype "passive"))
      (node (ref "R25") (pin "1") (pinfunction "1_1") (pintype "passive"))
      (node (ref "R26") (pin "1") (pinfunction "1_1") (pintype "passive"))
      (node (ref "U5") (pin "6") (pinfunction "OUT_6") (pintype "output"))
    )
    (net (code "9") (name "/Cont_I2_gain") (class "Default")
      (node (ref "RS5") (pin "9") (pinfunction "Coil-_9") (pintype "passive"))
      (node (ref "UD1") (pin "15") (pinfunction "OT2_15") (pintype "input"))
    )
    (net (code "10") (name "/Cont_I3") (class "Default")
      (node (ref "JP6") (pin "2") (pinfunction "2_2") (pintype "passive"))
      (node (ref "R43") (pin "1") (pinfunction "1_1") (pintype "passive"))
      (node (ref "RS6") (pin "1") (pinfunction "NC_1") (pintype "passive"))
      (node (ref "U8") (pin "6") (pinfunction "OUT_6") (pintype "output"))
    )
    (net (code "11") (name "/Cont_I3_gain") (class "Default")
      (node (ref "RS6") (pin "9") (pinfunction "Coil-_9") (pintype "passive"))
      (node (ref "UD4") (pin "10") (pinfunction "OT7_10") (pintype "input"))
    )
    (net (code "12") (name "/Cont_V1") (class "Default")
      (node (ref "JP3") (pin "2") (pinfunction "2_2") (pintype "passive"))
      (node (ref "U1") (pin "2") (pinfunction "-IN_2") (pintype "passive"))
      (node (ref "U1") (pin "6") (pinfunction "OUT_6") (pintype "output"))
    )
    (net (code "13") (name "/Cont_V1_gain") (class "Default")
      (node (ref "RS1") (pin "10") (pinfunction "Coil-_10") (pintype "passive"))
      (node (ref "UD1") (pin "14") (pinfunction "OT3_14") (pintype "tri_state"))
    )
    (net (code "14") (name "/Cont_V1_in") (class "Default")
      (node (ref "R19") (pin "1") (pinfunction "1_1") (pintype "passive"))
      (node (ref "RS1") (pin "3") (pinfunction "COM_3") (pintype "passive"))
      (node (ref "RS1") (pin "8") (pinfunction "COM_8") (pintype "passive"))
    )
    (net (code "15") (name "/Cont_V2") (class "Default")
      (node (ref "JP5") (pin "2") (pinfunction "2_2") (pintype "passive"))
      (node (ref "U4") (pin "2") (pinfunction "-IN_2") (pintype "passive"))
      (node (ref "U4") (pin "6") (pinfunction "OUT_6") (pintype "output"))
    )
    (net (code "16") (name "/Cont_V2_gain") (class "Default")
      (node (ref "RS2") (pin "10") (pinfunction "Coil-_10") (pintype "passive"))
      (node (ref "UD1") (pin "13") (pinfunction "OT4_13") (pintype "input"))
    )
    (net (code "17") (name "/Cont_V2_in") (class "Default")
      (node (ref "R37") (pin "1") (pinfunction "1_1") (pintype "passive"))
      (node (ref "RS2") (pin "3") (pinfunction "COM_3") (pintype "passive"))
      (node (ref "RS2") (pin "8") (pinfunction "COM_8") (pintype "passive"))
    )
    (net (code "18") (name "/Cont_V3") (class "Default")
      (node (ref "JP7") (pin "2") (pinfunction "2_2") (pintype "passive"))
      (node (ref "U7") (pin "2") (pinfunction "-IN_2") (pintype "passive"))
      (node (ref "U7") (pin "6") (pinfunction "OUT_6") (pintype "output"))
    )
    (net (code "19") (name "/Cont_V3_gain") (class "Default")
      (node (ref "RS3") (pin "10") (pinfunction "Coil-_10") (pintype "passive"))
      (node (ref "UD4") (pin "11") (pinfunction "OT6_11") (pintype "input"))
    )
    (net (code "20") (name "/Cont_V3_in") (class "Default")
      (node (ref "R53") (pin "1") (pinfunction "1_1") (pintype "passive"))
      (node (ref "RS3") (pin "3") (pinfunction "COM_3") (pintype "passive"))
      (node (ref "RS3") (pin "8") (pinfunction "COM_8") (pintype "passive"))
    )
    (net (code "21") (name "/aux1+") (class "Default")
      (node (ref "K1") (pin "3") (pinfunction "3_3") (pintype "passive"))
      (node (ref "K2") (pin "4") (pinfunction "4_4") (pintype "passive"))
      (node (ref "K3") (pin "3") (pinfunction "3_3") (pintype "passive"))
      (node (ref "K4") (pin "4") (pinfunction "4_4") (pintype "passive"))
      (node (ref "K5") (pin "3") (pinfunction "3_3") (pintype "passive"))
      (node (ref "K6") (pin "3") (pinfunction "3_3") (pintype "passive"))
      (node (ref "K7") (pin "3") (pinfunction "3_3") (pintype "passive"))
      (node (ref "R9") (pin "1") (pinfunction "1_1") (pintype "passive"))
      (node (ref "RS1") (pin "4") (pinfunction "NO_4") (pintype "passive"))
      (node (ref "RS1") (pin "7") (pinfunction "NO_7") (pintype "passive"))
    )
    (net (code "22") (name "/aux1+_28V") (class "Default")
      (node (ref "K2") (pin "3") (pinfunction "3_3") (pintype "passive"))
      (node (ref "Load_in") (pin "2") (pinfunction "2_2") (pintype "passive"))
    )
    (net (code "23") (name "/aux1-") (class "Default")
      (node (ref "C4") (pin "2") (pinfunction "2_2") (pintype "passive"))
      (node (ref "Cont-_5A") (pin "1") (pinfunction "1_1") (pintype "passive"))
      (node (ref "Cont-_5A") (pin "2") (pinfunction "2_2") (pintype "passive"))
      (node (ref "Cont-_5A") (pin "3") (pinfunction "3_3") (pintype "passive"))
      (node (ref "Cont-_5A") (pin "4") (pinfunction "4_4") (pintype "passive"))
      (node (ref "Cont-_5A") (pin "5") (pinfunction "5_5") (pintype "passive"))
      (node (ref "R18") (pin "2") (pinfunction "2_2") (pintype "passive"))
      (node (ref "R21") (pin "2") (pinfunction "2_2") (pintype "passive"))
    )
    (net (code "24") (name "/aux1.1+") (class "Default")
      (node (ref "Cont+_5A") (pin "1") (pinfunction "1_1") (pintype "passive"))
      (node (ref "K1") (pin "4") (pinfunction "4_4") (pintype "passive"))
    )
    (net (code "25") (name "/aux1.1_IO") (class "Default")
      (node (ref "DB1") (pin "21") (pinfunction "21_21") (pintype "passive"))
      (node (ref "UD3") (pin "5") (pinfunction "IN5_5") (pintype "input"))
    )
    (net (code "26") (name "/aux1.1_ctrl") (class "Default")
      (node (ref "K1") (pin "1") (pinfunction "1_1") (pintype "passive"))
      (node (ref "UD3") (pin "12") (pinfunction "OT5_12") (pintype "input"))
    )
    (net (code "27") (name "/aux1.2+") (class "Default")
      (node (ref "Cont+_5A") (pin "2") (pinfunction "2_2") (pintype "passive"))
      (node (ref "K3") (pin "4") (pinfunction "4_4") (pintype "passive"))
    )
    (net (code "28") (name "/aux1.2_IO") (class "Default")
      (node (ref "DB1") (pin "8") (pinfunction "8_8") (pintype "passive"))
      (node (ref "UD3") (pin "4") (pinfunction "IN4_4") (pintype "input"))
    )
    (net (code "29") (name "/aux1.2_ctrl") (class "Default")
      (node (ref "K3") (pin "1") (pinfunction "1_1") (pintype "passive"))
      (node (ref "UD3") (pin "13") (pinfunction "OT4_13") (pintype "input"))
    )
    (net (code "30") (name "/aux1.3+") (class "Default")
      (node (ref "Cont+_5A") (pin "3") (pinfunction "3_3") (pintype "passive"))
      (node (ref "K5") (pin "4") (pinfunction "4_4") (pintype "passive"))
    )
    (net (code "31") (name "/aux1.3_IO") (class "Default")
      (node (ref "DB1") (pin "20") (pinfunction "20_20") (pintype "passive"))
      (node (ref "UD3") (pin "3") (pinfunction "IN3_3") (pintype "input"))
    )
    (net (code "32") (name "/aux1.3_ctrl") (class "Default")
      (node (ref "K5") (pin "1") (pinfunction "1_1") (pintype "passive"))
      (node (ref "UD3") (pin "14") (pinfunction "OT3_14") (pintype "tri_state"))
    )
    (net (code "33") (name "/aux1.4+") (class "Default")
      (node (ref "Cont+_5A") (pin "4") (pinfunction "4_4") (pintype "passive"))
      (node (ref "K6") (pin "4") (pinfunction "4_4") (pintype "passive"))
    )
    (net (code "34") (name "/aux1.4_IO") (class "Default")
      (node (ref "DB1") (pin "7") (pinfunction "7_7") (pintype "passive"))
      (node (ref "UD3") (pin "2") (pinfunction "IN2_2") (pintype "input"))
    )
    (net (code "35") (name "/aux1.4_ctrl") (class "Default")
      (node (ref "K6") (pin "1") (pinfunction "1_1") (pintype "passive"))
      (node (ref "UD3") (pin "15") (pinfunction "OT2_15") (pintype "input"))
    )
    (net (code "36") (name "/aux1.5+") (class "Default")
      (node (ref "Cont+_5A") (pin "5") (pinfunction "5_5") (pintype "passive"))
      (node (ref "K7") (pin "4") (pinfunction "4_4") (pintype "passive"))
    )
    (net (code "37") (name "/aux1.5_IO") (class "Default")
      (node (ref "DB1") (pin "19") (pinfunction "19_19") (pintype "passive"))
      (node (ref "UD3") (pin "1") (pinfunction "IN1_1") (pintype "input"))
    )
    (net (code "38") (name "/aux1.5_ctrl") (class "Default")
      (node (ref "K7") (pin "1") (pinfunction "1_1") (pintype "passive"))
      (node (ref "UD3") (pin "16") (pinfunction "OT1_16") (pintype "power_in"))
    )
    (net (code "39") (name "/aux1_6V_IO") (class "Default")
      (node (ref "DB1") (pin "3") (pinfunction "3_3") (pintype "passive"))
      (node (ref "UD2") (pin "1") (pinfunction "IN1_1") (pintype "input"))
    )
    (net (code "40") (name "/aux1_6V_ctrl") (class "Default")
      (node (ref "K4") (pin "1") (pinfunction "1_1") (pintype "passive"))
      (node (ref "UD2") (pin "16") (pinfunction "OT1_16") (pintype "power_in"))
    )
    (net (code "41") (name "/aux1_28V_IO") (class "Default")
      (node (ref "DB1") (pin "16") (pinfunction "16_16") (pintype "passive"))
      (node (ref "UD2") (pin "2") (pinfunction "IN2_2") (pintype "input"))
    )
    (net (code "42") (name "/aux1_28V_ctrl") (class "Default")
      (node (ref "K2") (pin "1") (pinfunction "1_1") (pintype "passive"))
      (node (ref "UD2") (pin "15") (pinfunction "OT2_15") (pintype "input"))
    )
    (net (code "43") (name "/aux2+") (class "Default")
      (node (ref "K10") (pin "3") (pinfunction "3_3") (pintype "passive"))
      (node (ref "K11") (pin "4") (pinfunction "4_4") (pintype "passive"))
      (node (ref "K12") (pin "3") (pinfunction "3_3") (pintype "passive"))
      (node (ref "K13") (pin "3") (pinfunction "3_3") (pintype "passive"))
      (node (ref "K14") (pin "3") (pinfunction "3_3") (pintype "passive"))
      (node (ref "K8") (pin "3") (pinfunction "3_3") (pintype "passive"))
      (node (ref "K9") (pin "4") (pinfunction "4_4") (pintype "passive"))
      (node (ref "R27") (pin "1") (pinfunction "1_1") (pintype "passive"))
      (node (ref "RS2") (pin "4") (pinfunction "NO_4") (pintype "passive"))
      (node (ref "RS2") (pin "7") (pinfunction "NO_7") (pintype "passive"))
    )
    (net (code "44") (name "/aux2+_28V") (class "Default")
      (node (ref "K9") (pin "3") (pinfunction "3_3") (pintype "passive"))
      (node (ref "Load_in") (pin "3") (pinfunction "3_3") (pintype "passive"))
    )
    (net (code "45") (name "/aux2-") (class "Default")
      (node (ref "C11") (pin "2") (pinfunction "2_2") (pintype "passive"))
      (node (ref "Cont-_5A") (pin "10") (pinfunction "10_10") (pintype "passive"))
      (node (ref "Cont-_5A") (pin "6") (pinfunction "6_6") (pintype "passive"))
      (node (ref "Cont-_5A") (pin "7") (pinfunction "7_7") (pintype "passive"))
      (node (ref "Cont-_5A") (pin "8") (pinfunction "8_8") (pintype "passive"))
      (node (ref "Cont-_5A") (pin "9") (pinfunction "9_9") (pintype "passive"))
      (node (ref "R36") (pin "2") (pinfunction "2_2") (pintype "passive"))
      (node (ref "R39") (pin "2") (pinfunction "2_2") (pintype "passive"))
    )
    (net (code "46") (name "/aux2.1+") (class "Default")
      (node (ref "Cont+_5A") (pin "6") (pinfunction "6_6") (pintype "passive"))
      (node (ref "K8") (pin "4") (pinfunction "4_4") (pintype "passive"))
    )
    (net (code "47") (name "/aux2.1_IO") (class "Default")
      (node (ref "DB1") (pin "6") (pinfunction "6_6") (pintype "passive"))
      (node (ref "UD2") (pin "7") (pinfunction "IN7_7") (pintype "input"))
    )
    (net (code "48") (name "/aux2.1_ctrl") (class "Default")
      (node (ref "K8") (pin "1") (pinfunction "1_1") (pintype "passive"))
      (node (ref "UD2") (pin "10") (pinfunction "OT7_10") (pintype "input"))
    )
    (net (code "49") (name "/aux2.2+") (class "Default")
      (node (ref "Cont+_5A") (pin "7") (pinfunction "7_7") (pintype "passive"))
      (node (ref "K10") (pin "4") (pinfunction "4_4") (pintype "passive"))
    )
    (net (code "50") (name "/aux2.2_IO") (class "Default")
      (node (ref "DB1") (pin "18") (pinfunction "18_18") (pintype "passive"))
      (node (ref "UD2") (pin "6") (pinfunction "IN6_6") (pintype "input"))
    )
    (net (code "51") (name "/aux2.2_ctrl") (class "Default")
      (node (ref "K10") (pin "1") (pinfunction "1_1") (pintype "passive"))
      (node (ref "UD2") (pin "11") (pinfunction "OT6_11") (pintype "input"))
    )
    (net (code "52") (name "/aux2.3+") (class "Default")
      (node (ref "Cont+_5A") (pin "8") (pinfunction "8_8") (pintype "passive"))
      (node (ref "K12") (pin "4") (pinfunction "4_4") (pintype "passive"))
    )
    (net (code "53") (name "/aux2.3_IO") (class "Default")
      (node (ref "DB1") (pin "5") (pinfunction "5_5") (pintype "passive"))
      (node (ref "UD2") (pin "5") (pinfunction "IN5_5") (pintype "input"))
    )
    (net (code "54") (name "/aux2.3_ctrl") (class "Default")
      (node (ref "K12") (pin "1") (pinfunction "1_1") (pintype "passive"))
      (node (ref "UD2") (pin "12") (pinfunction "OT5_12") (pintype "input"))
    )
    (net (code "55") (name "/aux2.4+") (class "Default")
      (node (ref "Cont+_5A") (pin "9") (pinfunction "9_9") (pintype "passive"))
      (node (ref "K13") (pin "4") (pinfunction "4_4") (pintype "passive"))
    )
    (net (code "56") (name "/aux2.4_IO") (class "Default")
      (node (ref "DB1") (pin "17") (pinfunction "17_17") (pintype "passive"))
      (node (ref "UD2") (pin "4") (pinfunction "IN4_4") (pintype "input"))
    )
    (net (code "57") (name "/aux2.4_ctrl") (class "Default")
      (node (ref "K13") (pin "1") (pinfunction "1_1") (pintype "passive"))
      (node (ref "UD2") (pin "13") (pinfunction "OT4_13") (pintype "input"))
    )
    (net (code "58") (name "/aux2.5+") (class "Default")
      (node (ref "Cont+_5A") (pin "10") (pinfunction "10_10") (pintype "passive"))
      (node (ref "K14") (pin "4") (pinfunction "4_4") (pintype "passive"))
    )
    (net (code "59") (name "/aux2.5_IO") (class "Default")
      (node (ref "DB1") (pin "4") (pinfunction "4_4") (pintype "passive"))
      (node (ref "UD2") (pin "3") (pinfunction "IN3_3") (pintype "input"))
    )
    (net (code "60") (name "/aux2.5_ctrl") (class "Default")
      (node (ref "K14") (pin "1") (pinfunction "1_1") (pintype "passive"))
      (node (ref "UD2") (pin "14") (pinfunction "OT3_14") (pintype "tri_state"))
    )
    (net (code "61") (name "/aux2_6V_IO") (class "Default")
      (node (ref "DB1") (pin "2") (pinfunction "2_2") (pintype "passive"))
      (node (ref "UD1") (pin "5") (pinfunction "IN5_5") (pintype "input"))
    )
    (net (code "62") (name "/aux2_6V_ctrl") (class "Default")
      (node (ref "K11") (pin "1") (pinfunction "1_1") (pintype "passive"))
      (node (ref "UD1") (pin "12") (pinfunction "OT5_12") (pintype "input"))
    )
    (net (code "63") (name "/aux2_28V_IO") (class "Default")
      (node (ref "DB1") (pin "15") (pinfunction "15_15") (pintype "passive"))
      (node (ref "UD1") (pin "6") (pinfunction "IN6_6") (pintype "input"))
    )
    (net (code "64") (name "/aux2_28V_ctrl") (class "Default")
      (node (ref "K9") (pin "1") (pinfunction "1_1") (pintype "passive"))
      (node (ref "UD1") (pin "11") (pinfunction "OT6_11") (pintype "input"))
    )
    (net (code "65") (name "/main+") (class "Default")
      (node (ref "K15") (pin "2") (pinfunction "2_2") (pintype "passive"))
      (node (ref "K16") (pin "3") (pinfunction "3_3") (pintype "passive"))
      (node (ref "K17") (pin "2") (pinfunction "2_2") (pintype "passive"))
      (node (ref "K18") (pin "3") (pinfunction "3_3") (pintype "passive"))
      (node (ref "K19") (pin "2") (pinfunction "2_2") (pintype "passive"))
      (node (ref "K20") (pin "2") (pinfunction "2_2") (pintype "passive"))
      (node (ref "K21") (pin "2") (pinfunction "2_2") (pintype "passive"))
      (node (ref "R44") (pin "1") (pinfunction "1_1") (pintype "passive"))
      (node (ref "RS3") (pin "4") (pinfunction "NO_4") (pintype "passive"))
      (node (ref "RS3") (pin "7") (pinfunction "NO_7") (pintype "passive"))
    )
    (net (code "66") (name "/main+_270V") (class "Default")
      (node (ref "K16") (pin "2") (pinfunction "2_2") (pintype "passive"))
      (node (ref "Load_in") (pin "1") (pinfunction "1_1") (pintype "passive"))
    )
    (net (code "67") (name "/main-") (class "Default")
      (node (ref "C18") (pin "2") (pinfunction "2_2") (pintype "passive"))
      (node (ref "Cont-_10A") (pin "1") (pinfunction "1_1") (pintype "passive"))
      (node (ref "Cont-_10A") (pin "2") (pinfunction "2_2") (pintype "passive"))
      (node (ref "Cont-_10A") (pin "3") (pinfunction "3_3") (pintype "passive"))
      (node (ref "Cont-_10A") (pin "4") (pinfunction "4_4") (pintype "passive"))
      (node (ref "Cont-_10A") (pin "5") (pinfunction "5_5") (pintype "passive"))
      (node (ref "R55") (pin "2") (pinfunction "2_2") (pintype "passive"))
      (node (ref "R56") (pin "2") (pinfunction "2_2") (pintype "passive"))
    )
    (net (code "68") (name "/main.1+") (class "Default")
      (node (ref "Cont+_10A") (pin "5") (pinfunction "5_5") (pintype "passive"))
      (node (ref "K15") (pin "3") (pinfunction "3_3") (pintype "passive"))
    )
    (net (code "69") (name "/main.1_IO") (class "Default")
      (node (ref "DB1") (pin "10") (pinfunction "10_10") (pintype "passive"))
      (node (ref "UD4") (pin "1") (pinfunction "IN1_1") (pintype "input"))
    )
    (net (code "70") (name "/main.1_ctrl") (class "Default")
      (node (ref "K15") (pin "5") (pinfunction "5_5") (pintype "passive"))
      (node (ref "UD4") (pin "16") (pinfunction "OT1_16") (pintype "power_in"))
    )
    (net (code "71") (name "/main.2+") (class "Default")
      (node (ref "Cont+_10A") (pin "4") (pinfunction "4_4") (pintype "passive"))
      (node (ref "K17") (pin "3") (pinfunction "3_3") (pintype "passive"))
    )
    (net (code "72") (name "/main.2_IO") (class "Default")
      (node (ref "DB1") (pin "23") (pinfunction "23_23") (pintype "passive"))
      (node (ref "UD4") (pin "2") (pinfunction "IN2_2") (pintype "input"))
    )
    (net (code "73") (name "/main.2_ctrl") (class "Default")
      (node (ref "K17") (pin "5") (pinfunction "5_5") (pintype "passive"))
      (node (ref "UD4") (pin "15") (pinfunction "OT2_15") (pintype "input"))
    )
    (net (code "74") (name "/main.3+") (class "Default")
      (node (ref "Cont+_10A") (pin "3") (pinfunction "3_3") (pintype "passive"))
      (node (ref "K19") (pin "3") (pinfunction "3_3") (pintype "passive"))
    )
    (net (code "75") (name "/main.3_IO") (class "Default")
      (node (ref "DB1") (pin "11") (pinfunction "11_11") (pintype "passive"))
      (node (ref "UD4") (pin "3") (pinfunction "IN3_3") (pintype "input"))
    )
    (net (code "76") (name "/main.3_ctrl") (class "Default")
      (node (ref "K19") (pin "5") (pinfunction "5_5") (pintype "passive"))
      (node (ref "UD4") (pin "14") (pinfunction "OT3_14") (pintype "tri_state"))
    )
    (net (code "77") (name "/main.4+") (class "Default")
      (node (ref "Cont+_10A") (pin "2") (pinfunction "2_2") (pintype "passive"))
      (node (ref "K20") (pin "3") (pinfunction "3_3") (pintype "passive"))
    )
    (net (code "78") (name "/main.4_IO") (class "Default")
      (node (ref "DB1") (pin "24") (pinfunction "24_24") (pintype "passive"))
      (node (ref "UD4") (pin "4") (pinfunction "IN4_4") (pintype "input"))
    )
    (net (code "79") (name "/main.4_ctrl") (class "Default")
      (node (ref "K20") (pin "5") (pinfunction "5_5") (pintype "passive"))
      (node (ref "UD4") (pin "13") (pinfunction "OT4_13") (pintype "input"))
    )
    (net (code "80") (name "/main.5+") (class "Default")
      (node (ref "Cont+_10A") (pin "1") (pinfunction "1_1") (pintype "passive"))
      (node (ref "K21") (pin "3") (pinfunction "3_3") (pintype "passive"))
    )
    (net (code "81") (name "/main.5_IO") (class "Default")
      (node (ref "DB1") (pin "12") (pinfunction "12_12") (pintype "passive"))
      (node (ref "UD4") (pin "5") (pinfunction "IN5_5") (pintype "input"))
    )
    (net (code "82") (name "/main.5_ctrl") (class "Default")
      (node (ref "K21") (pin "5") (pinfunction "5_5") (pintype "passive"))
      (node (ref "UD4") (pin "12") (pinfunction "OT5_12") (pintype "input"))
    )
    (net (code "83") (name "/main_6V_IO") (class "Default")
      (node (ref "DB1") (pin "22") (pinfunction "22_22") (pintype "passive"))
      (node (ref "UD3") (pin "7") (pinfunction "IN7_7") (pintype "input"))
    )
    (net (code "84") (name "/main_6V_ctrl") (class "Default")
      (node (ref "K18") (pin "5") (pinfunction "5_5") (pintype "passive"))
      (node (ref "UD3") (pin "10") (pinfunction "OT7_10") (pintype "input"))
    )
    (net (code "85") (name "/main_270V_IO") (class "Default")
      (node (ref "DB1") (pin "9") (pinfunction "9_9") (pintype "passive"))
      (node (ref "UD3") (pin "6") (pinfunction "IN6_6") (pintype "input"))
    )
    (net (code "86") (name "/main_270V_ctrl") (class "Default")
      (node (ref "K16") (pin "5") (pinfunction "5_5") (pintype "passive"))
      (node (ref "UD3") (pin "11") (pinfunction "OT6_11") (pintype "input"))
    )
    (net (code "87") (name "5V") (class "Default")
      (node (ref "C1_5") (pin "1") (pinfunction "A_1") (pintype "passive"))
      (node (ref "C2_5") (pin "1") (pintype "passive"))
      (node (ref "C3_5") (pin "1") (pintype "passive"))
      (node (ref "C4_5") (pin "1") (pintype "passive"))
      (node (ref "K1") (pin "2") (pinfunction "2_2") (pintype "passive"))
      (node (ref "K10") (pin "2") (pinfunction "2_2") (pintype "passive"))
      (node (ref "K11") (pin "2") (pinfunction "2_2") (pintype "passive"))
      (node (ref "K12") (pin "2") (pinfunction "2_2") (pintype "passive"))
      (node (ref "K13") (pin "2") (pinfunction "2_2") (pintype "passive"))
      (node (ref "K14") (pin "2") (pinfunction "2_2") (pintype "passive"))
      (node (ref "K15") (pin "1") (pinfunction "1_1") (pintype "passive"))
      (node (ref "K16") (pin "1") (pinfunction "1_1") (pintype "passive"))
      (node (ref "K17") (pin "1") (pinfunction "1_1") (pintype "passive"))
      (node (ref "K18") (pin "1") (pinfunction "1_1") (pintype "passive"))
      (node (ref "K19") (pin "1") (pinfunction "1_1") (pintype "passive"))
      (node (ref "K2") (pin "2") (pinfunction "2_2") (pintype "passive"))
      (node (ref "K20") (pin "1") (pinfunction "1_1") (pintype "passive"))
      (node (ref "K21") (pin "1") (pinfunction "1_1") (pintype "passive"))
      (node (ref "K3") (pin "2") (pinfunction "2_2") (pintype "passive"))
      (node (ref "K4") (pin "2") (pinfunction "2_2") (pintype "passive"))
      (node (ref "K5") (pin "2") (pinfunction "2_2") (pintype "passive"))
      (node (ref "K6") (pin "2") (pinfunction "2_2") (pintype "passive"))
      (node (ref "K7") (pin "2") (pinfunction "2_2") (pintype "passive"))
      (node (ref "K8") (pin "2") (pinfunction "2_2") (pintype "passive"))
      (node (ref "K9") (pin "2") (pinfunction "2_2") (pintype "passive"))
      (node (ref "PWR") (pin "3") (pinfunction "3_3") (pintype "passive"))
      (node (ref "R6") (pin "2") (pinfunction "2_2") (pintype "passive"))
      (node (ref "RS1") (pin "1") (pinfunction "Coil+_1") (pintype "passive"))
      (node (ref "RS2") (pin "1") (pinfunction "Coil+_1") (pintype "passive"))
      (node (ref "RS3") (pin "1") (pinfunction "Coil+_1") (pintype "passive"))
      (node (ref "RS4") (pin "2") (pinfunction "Coil+_2") (pintype "passive"))
      (node (ref "RS5") (pin "2") (pinfunction "Coil+_2") (pintype "passive"))
      (node (ref "RS6") (pin "2") (pinfunction "Coil+_2") (pintype "passive"))
      (node (ref "UD1") (pin "9") (pinfunction "COM_9") (pintype "input"))
      (node (ref "UD2") (pin "9") (pinfunction "COM_9") (pintype "input"))
      (node (ref "UD3") (pin "9") (pinfunction "COM_9") (pintype "input"))
      (node (ref "UD4") (pin "9") (pinfunction "COM_9") (pintype "input"))
    )
    (net (code "88") (name "6V") (class "Default")
      (node (ref "R12") (pin "1") (pinfunction "1_1") (pintype "passive"))
      (node (ref "R30") (pin "1") (pinfunction "1_1") (pintype "passive"))
      (node (ref "R50") (pin "2") (pinfunction "2_2") (pintype "passive"))
      (node (ref "TPS1") (pin "1") (pinfunction "OUT+_1") (pintype "passive"))
    )
    (net (code "89") (name "28V") (class "Default")
      (node (ref "C1_28") (pin "1") (pinfunction "A_1") (pintype "passive"))
      (node (ref "C2_28") (pin "1") (pintype "passive"))
      (node (ref "C3_28") (pin "1") (pintype "passive"))
      (node (ref "C4_28") (pin "1") (pintype "passive"))
      (node (ref "PWR") (pin "1") (pinfunction "1_1") (pintype "passive"))
      (node (ref "R3") (pin "2") (pinfunction "2_2") (pintype "passive"))
      (node (ref "TPS1") (pin "5") (pinfunction "VCC_5") (pintype "passive"))
    )
    (net (code "90") (name "GND_5") (class "Default")
      (node (ref "5") (pin "2") (pinfunction "K_2") (pintype "passive"))
      (node (ref "C1_5") (pin "2") (pinfunction "K_2") (pintype "passive"))
      (node (ref "C2_5") (pin "2") (pintype "passive"))
      (node (ref "C3_5") (pin "2") (pintype "passive"))
      (node (ref "C4_5") (pin "2") (pintype "passive"))
      (node (ref "PWR") (pin "4") (pinfunction "4_4") (pintype "passive"))
      (node (ref "R4") (pin "1") (pinfunction "1_1") (pintype "passive"))
      (node (ref "UD1") (pin "8") (pinfunction "GND_8") (pintype "power_in"))
      (node (ref "UD2") (pin "8") (pinfunction "GND_8") (pintype "power_in"))
      (node (ref "UD3") (pin "8") (pinfunction "GND_8") (pintype "power_in"))
      (node (ref "UD4") (pin "8") (pinfunction "GND_8") (pintype "power_in"))
    )
    (net (code "91") (name "GND_12") (class "Default")
      (node (ref "+12") (pin "2") (pinfunction "K_2") (pintype "passive"))
      (node (ref "-12") (pin "1") (pinfunction "A_1") (pintype "passive"))
      (node (ref "C1") (pin "2") (pinfunction "2_2") (pintype "passive"))
      (node (ref "C10") (pin "2") (pinfunction "2_2") (pintype "passive"))
      (node (ref "C11") (pin "1") (pinfunction "1_1") (pintype "passive"))
      (node (ref "C12") (pin "2") (pinfunction "2_2") (pintype "passive"))
      (node (ref "C13") (pin "2") (pinfunction "2_2") (pintype "passive"))
      (node (ref "C14") (pin "2") (pinfunction "2_2") (pintype "passive"))
      (node (ref "C15") (pin "2") (pinfunction "2_2") (pintype "passive"))
      (node (ref "C16") (pin "2") (pinfunction "2_2") (pintype "passive"))
      (node (ref "C17") (pin "2") (pinfunction "2_2") (pintype "passive"))
      (node (ref "C18") (pin "1") (pinfunction "1_1") (pintype "passive"))
      (node (ref "C19") (pin "2") (pinfunction "2_2") (pintype "passive"))
      (node (ref "C1_+12") (pin "2") (pinfunction "K_2") (pintype "passive"))
      (node (ref "C1_-12") (pin "1") (pinfunction "A_1") (pintype "passive"))
      (node (ref "C2") (pin "2") (pinfunction "2_2") (pintype "passive"))
      (node (ref "C20") (pin "2") (pinfunction "2_2") (pintype "passive"))
      (node (ref "C21") (pin "2") (pinfunction "2_2") (pintype "passive"))
      (node (ref "C2_+12") (pin "2") (pintype "passive"))
      (node (ref "C2_-12") (pin "1") (pintype "passive"))
      (node (ref "C3") (pin "2") (pinfunction "2_2") (pintype "passive"))
      (node (ref "C3_+12") (pin "2") (pintype "passive"))
      (node (ref "C3_-12") (pin "1") (pintype "passive"))
      (node (ref "C4") (pin "1") (pinfunction "1_1") (pintype "passive"))
      (node (ref "C4_+12") (pin "2") (pintype "passive"))
      (node (ref "C4_-12") (pin "1") (pintype "passive"))
      (node (ref "C5") (pin "2") (pinfunction "2_2") (pintype "passive"))
      (node (ref "C6") (pin "2") (pinfunction "2_2") (pintype "passive"))
      (node (ref "C7") (pin "2") (pinfunction "2_2") (pintype "passive"))
      (node (ref "C8") (pin "2") (pinfunction "2_2") (pintype "passive"))
      (node (ref "C9") (pin "2") (pinfunction "2_2") (pintype "passive"))
      (node (ref "E1") (pin "2") (pinfunction "K_2") (pintype "passive"))
      (node (ref "E10") (pin "1") (pinfunction "A_1") (pintype "passive"))
      (node (ref "E11") (pin "1") (pinfunction "A_1") (pintype "passive"))
      (node (ref "E12") (pin "1") (pinfunction "A_1") (pintype "passive"))
      (node (ref "E13") (pin "2") (pinfunction "K_2") (pintype "passive"))
      (node (ref "E14") (pin "2") (pinfunction "K_2") (pintype "passive"))
      (node (ref "E15") (pin "2") (pinfunction "K_2") (pintype "passive"))
      (node (ref "E16") (pin "1") (pinfunction "A_1") (pintype "passive"))
      (node (ref "E17") (pin "1") (pinfunction "A_1") (pintype "passive"))
      (node (ref "E18") (pin "1") (pinfunction "A_1") (pintype "passive"))
      (node (ref "E2") (pin "2") (pinfunction "K_2") (pintype "passive"))
      (node (ref "E3") (pin "2") (pinfunction "K_2") (pintype "passive"))
      (node (ref "E4") (pin "1") (pinfunction "A_1") (pintype "passive"))
      (node (ref "E5") (pin "1") (pinfunction "A_1") (pintype "passive"))
      (node (ref "E6") (pin "1") (pinfunction "A_1") (pintype "passive"))
      (node (ref "E7") (pin "2") (pinfunction "K_2") (pintype "passive"))
      (node (ref "E8") (pin "2") (pinfunction "K_2") (pintype "passive"))
      (node (ref "E9") (pin "2") (pinfunction "K_2") (pintype "passive"))
      (node (ref "JP2") (pin "1") (pinfunction "1_1") (pintype "passive"))
      (node (ref "JP3") (pin "1") (pinfunction "1_1") (pintype "passive"))
      (node (ref "JP4") (pin "1") (pinfunction "1_1") (pintype "passive"))
      (node (ref "JP5") (pin "1") (pinfunction "1_1") (pintype "passive"))
      (node (ref "JP6") (pin "1") (pinfunction "1_1") (pintype "passive"))
      (node (ref "JP7") (pin "1") (pinfunction "1_1") (pintype "passive"))
      (node (ref "PWR") (pin "6") (pinfunction "6_6") (pintype "passive"))
      (node (ref "R13") (pin "2") (pinfunction "2_2") (pintype "passive"))
      (node (ref "R17") (pin "2") (pinfunction "2_2") (pintype "passive"))
      (node (ref "R31") (pin "2") (pinfunction "2_2") (pintype "passive"))
      (node (ref "R35") (pin "2") (pinfunction "2_2") (pintype "passive"))
      (node (ref "R4") (pin "2") (pinfunction "2_2") (pintype "passive"))
      (node (ref "R47") (pin "2") (pinfunction "2_2") (pintype "passive"))
      (node (ref "R5") (pin "1") (pinfunction "1_1") (pintype "passive"))
      (node (ref "R52") (pin "2") (pinfunction "2_2") (pintype "passive"))
      (node (ref "U3") (pin "5") (pinfunction "REF_5") (pintype "input"))
      (node (ref "U6") (pin "5") (pinfunction "REF_5") (pintype "input"))
      (node (ref "U9") (pin "5") (pinfunction "REF_5") (pintype "input"))
    )
    (net (code "92") (name "GND_28") (class "Default")
      (node (ref "28") (pin "2") (pinfunction "K_2") (pintype "passive"))
      (node (ref "C1_28") (pin "2") (pinfunction "K_2") (pintype "passive"))
      (node (ref "C2_28") (pin "2") (pintype "passive"))
      (node (ref "C3_28") (pin "2") (pintype "passive"))
      (node (ref "C4_28") (pin "2") (pintype "passive"))
      (node (ref "PWR") (pin "2") (pinfunction "2_2") (pintype "passive"))
      (node (ref "R10") (pin "1") (pinfunction "1_1") (pintype "passive"))
      (node (ref "R17") (pin "1") (pinfunction "1_1") (pintype "passive"))
      (node (ref "R18") (pin "1") (pinfunction "1_1") (pintype "passive"))
      (node (ref "R28") (pin "1") (pinfunction "1_1") (pintype "passive"))
      (node (ref "R35") (pin "1") (pinfunction "1_1") (pintype "passive"))
      (node (ref "R36") (pin "1") (pinfunction "1_1") (pintype "passive"))
      (node (ref "R45") (pin "1") (pinfunction "1_1") (pintype "passive"))
      (node (ref "R5") (pin "2") (pinfunction "2_2") (pintype "passive"))
      (node (ref "R52") (pin "1") (pinfunction "1_1") (pintype "passive"))
      (node (ref "R55") (pin "1") (pinfunction "1_1") (pintype "passive"))
      (node (ref "TPS1") (pin "2") (pinfunction "GND_2") (pintype "passive"))
      (node (ref "TPS1") (pin "4") (pinfunction "GND_4") (pintype "passive"))
      (node (ref "U3") (pin "2") (pinfunction "-IN_2") (pintype "passive"))
      (node (ref "U6") (pin "2") (pinfunction "-IN_2") (pintype "passive"))
      (node (ref "U9") (pin "2") (pinfunction "-IN_2") (pintype "passive"))
    )
    (net (code "93") (name "Net-(+12-A)") (class "Default")
      (node (ref "+12") (pin "1") (pinfunction "A_1") (pintype "passive"))
      (node (ref "R2") (pin "1") (pinfunction "1_1") (pintype "passive"))
    )
    (net (code "94") (name "Net-(-12-K)") (class "Default")
      (node (ref "-12") (pin "2") (pinfunction "K_2") (pintype "passive"))
      (node (ref "R1") (pin "1") (pinfunction "1_1") (pintype "passive"))
    )
    (net (code "95") (name "Net-(5-A)") (class "Default")
      (node (ref "5") (pin "1") (pinfunction "A_1") (pintype "passive"))
      (node (ref "R6") (pin "1") (pinfunction "1_1") (pintype "passive"))
    )
    (net (code "96") (name "Net-(28-A)") (class "Default")
      (node (ref "28") (pin "1") (pinfunction "A_1") (pintype "passive"))
      (node (ref "R3") (pin "1") (pinfunction "1_1") (pintype "passive"))
    )
    (net (code "97") (name "Net-(D1-A)") (class "Default")
      (node (ref "D1") (pin "1") (pinfunction "A_1") (pintype "passive"))
      (node (ref "R19") (pin "2") (pinfunction "2_2") (pintype "passive"))
      (node (ref "U1") (pin "3") (pinfunction "+IN_3") (pintype "passive"))
    )
    (net (code "98") (name "Net-(D2-A)") (class "Default")
      (node (ref "D2") (pin "1") (pinfunction "A_1") (pintype "passive"))
      (node (ref "R21") (pin "1") (pinfunction "1_1") (pintype "passive"))
      (node (ref "U3") (pin "3") (pinfunction "+IN_3") (pintype "passive"))
    )
    (net (code "99") (name "Net-(D3-A)") (class "Default")
      (node (ref "D3") (pin "1") (pinfunction "A_1") (pintype "passive"))
      (node (ref "R37") (pin "2") (pinfunction "2_2") (pintype "passive"))
      (node (ref "U4") (pin "3") (pinfunction "+IN_3") (pintype "passive"))
    )
    (net (code "100") (name "Net-(D4-A)") (class "Default")
      (node (ref "D4") (pin "1") (pinfunction "A_1") (pintype "passive"))
      (node (ref "R39") (pin "1") (pinfunction "1_1") (pintype "passive"))
      (node (ref "U6") (pin "3") (pinfunction "+IN_3") (pintype "passive"))
    )
    (net (code "101") (name "Net-(D5-A)") (class "Default")
      (node (ref "D5") (pin "1") (pinfunction "A_1") (pintype "passive"))
      (node (ref "R53") (pin "2") (pinfunction "2_2") (pintype "passive"))
      (node (ref "U7") (pin "3") (pinfunction "+IN_3") (pintype "passive"))
    )
    (net (code "102") (name "Net-(D6-A)") (class "Default")
      (node (ref "D6") (pin "1") (pinfunction "A_1") (pintype "passive"))
      (node (ref "R56") (pin "1") (pinfunction "1_1") (pintype "passive"))
      (node (ref "U9") (pin "3") (pinfunction "+IN_3") (pintype "passive"))
    )
    (net (code "103") (name "Net-(K4-Pad3)") (class "Default")
      (node (ref "K4") (pin "3") (pinfunction "3_3") (pintype "passive"))
      (node (ref "R12") (pin "2") (pinfunction "2_2") (pintype "passive"))
    )
    (net (code "104") (name "Net-(K11-Pad3)") (class "Default")
      (node (ref "K11") (pin "3") (pinfunction "3_3") (pintype "passive"))
      (node (ref "R30") (pin "2") (pinfunction "2_2") (pintype "passive"))
    )
    (net (code "105") (name "Net-(K18-Pad2)") (class "Default")
      (node (ref "K18") (pin "2") (pinfunction "2_2") (pintype "passive"))
      (node (ref "R50") (pin "1") (pinfunction "1_1") (pintype "passive"))
    )
    (net (code "106") (name "Net-(R9-Pad2)") (class "Default")
      (node (ref "R9") (pin "2") (pinfunction "2_2") (pintype "passive"))
      (node (ref "RS1") (pin "2") (pinfunction "NC_2") (pintype "passive"))
    )
    (net (code "107") (name "Net-(R10-Pad2)") (class "Default")
      (node (ref "R10") (pin "2") (pinfunction "2_2") (pintype "passive"))
      (node (ref "RS1") (pin "9") (pinfunction "NC_9") (pintype "passive"))
    )
    (net (code "108") (name "Net-(R16-Pad1)") (class "Default")
      (node (ref "R16") (pin "1") (pinfunction "1_1") (pintype "passive"))
      (node (ref "U3") (pin "8") (pinfunction "RG_8") (pintype "passive"))
    )
    (net (code "109") (name "Net-(R16-Pad2)") (class "Default")
      (node (ref "R16") (pin "2") (pinfunction "2_2") (pintype "passive"))
      (node (ref "U3") (pin "1") (pinfunction "RG_1") (pintype "passive"))
    )
    (net (code "110") (name "Net-(R27-Pad2)") (class "Default")
      (node (ref "R27") (pin "2") (pinfunction "2_2") (pintype "passive"))
      (node (ref "RS2") (pin "2") (pinfunction "NC_2") (pintype "passive"))
    )
    (net (code "111") (name "Net-(R28-Pad2)") (class "Default")
      (node (ref "R28") (pin "2") (pinfunction "2_2") (pintype "passive"))
      (node (ref "RS2") (pin "9") (pinfunction "NC_9") (pintype "passive"))
    )
    (net (code "112") (name "Net-(R34-Pad1)") (class "Default")
      (node (ref "R34") (pin "1") (pinfunction "1_1") (pintype "passive"))
      (node (ref "U6") (pin "8") (pinfunction "RG_8") (pintype "passive"))
    )
    (net (code "113") (name "Net-(R34-Pad2)") (class "Default")
      (node (ref "R34") (pin "2") (pinfunction "2_2") (pintype "passive"))
      (node (ref "U6") (pin "1") (pinfunction "RG_1") (pintype "passive"))
    )
    (net (code "114") (name "Net-(R44-Pad2)") (class "Default")
      (node (ref "R44") (pin "2") (pinfunction "2_2") (pintype "passive"))
      (node (ref "RS3") (pin "2") (pinfunction "NC_2") (pintype "passive"))
    )
    (net (code "115") (name "Net-(R45-Pad2)") (class "Default")
      (node (ref "R45") (pin "2") (pinfunction "2_2") (pintype "passive"))
      (node (ref "RS3") (pin "9") (pinfunction "NC_9") (pintype "passive"))
    )
    (net (code "116") (name "Net-(R51-Pad1)") (class "Default")
      (node (ref "R51") (pin "1") (pinfunction "1_1") (pintype "passive"))
      (node (ref "U9") (pin "8") (pinfunction "RG_8") (pintype "passive"))
    )
    (net (code "117") (name "Net-(R51-Pad2)") (class "Default")
      (node (ref "R51") (pin "2") (pinfunction "2_2") (pintype "passive"))
      (node (ref "U9") (pin "1") (pinfunction "RG_1") (pintype "passive"))
    )
    (net (code "118") (name "Net-(RS4-COM1)") (class "Default")
      (node (ref "R13") (pin "1") (pinfunction "1_1") (pintype "passive"))
      (node (ref "RS4") (pin "5") (pinfunction "COM1_5") (pintype "passive"))
      (node (ref "RS4") (pin "6") (pinfunction "COM2_6") (pintype "passive"))
      (node (ref "U2") (pin "2") (pinfunction "-IN_2") (pintype "passive"))
    )
    (net (code "119") (name "Net-(RS4-NC)") (class "Default")
      (node (ref "R7") (pin "2") (pinfunction "2_2") (pintype "passive"))
      (node (ref "RS4") (pin "1") (pinfunction "NC_1") (pintype "passive"))
    )
    (net (code "120") (name "Net-(RS4-NO)") (class "Default")
      (node (ref "R8") (pin "2") (pinfunction "2_2") (pintype "passive"))
      (node (ref "RS4") (pin "10") (pinfunction "NO_10") (pintype "passive"))
    )
    (net (code "121") (name "Net-(RS5-COM1)") (class "Default")
      (node (ref "R31") (pin "1") (pinfunction "1_1") (pintype "passive"))
      (node (ref "RS5") (pin "5") (pinfunction "COM1_5") (pintype "passive"))
      (node (ref "RS5") (pin "6") (pinfunction "COM2_6") (pintype "passive"))
      (node (ref "U5") (pin "2") (pinfunction "-IN_2") (pintype "passive"))
    )
    (net (code "122") (name "Net-(RS5-NC)") (class "Default")
      (node (ref "R25") (pin "2") (pinfunction "2_2") (pintype "passive"))
      (node (ref "RS5") (pin "1") (pinfunction "NC_1") (pintype "passive"))
    )
    (net (code "123") (name "Net-(RS5-NO)") (class "Default")
      (node (ref "R26") (pin "2") (pinfunction "2_2") (pintype "passive"))
      (node (ref "RS5") (pin "10") (pinfunction "NO_10") (pintype "passive"))
    )
    (net (code "124") (name "Net-(RS6-COM1)") (class "Default")
      (node (ref "R47") (pin "1") (pinfunction "1_1") (pintype "passive"))
      (node (ref "RS6") (pin "5") (pinfunction "COM1_5") (pintype "passive"))
      (node (ref "RS6") (pin "6") (pinfunction "COM2_6") (pintype "passive"))
      (node (ref "U8") (pin "2") (pinfunction "-IN_2") (pintype "passive"))
    )
    (net (code "125") (name "Net-(RS6-NO)") (class "Default")
      (node (ref "R43") (pin "2") (pinfunction "2_2") (pintype "passive"))
      (node (ref "RS6") (pin "10") (pinfunction "NO_10") (pintype "passive"))
    )
    (net (code "126") (name "Net-(U2-+IN)") (class "Default")
      (node (ref "R20") (pin "2") (pinfunction "2_2") (pintype "passive"))
      (node (ref "U2") (pin "3") (pinfunction "+IN_3") (pintype "passive"))
    )
    (net (code "127") (name "Net-(U3-OUT)") (class "Default")
      (node (ref "R20") (pin "1") (pinfunction "1_1") (pintype "passive"))
      (node (ref "U3") (pin "6") (pinfunction "OUT_6") (pintype "output"))
    )
    (net (code "128") (name "Net-(U5-+IN)") (class "Default")
      (node (ref "R38") (pin "2") (pinfunction "2_2") (pintype "passive"))
      (node (ref "U5") (pin "3") (pinfunction "+IN_3") (pintype "passive"))
    )
    (net (code "129") (name "Net-(U6-OUT)") (class "Default")
      (node (ref "R38") (pin "1") (pinfunction "1_1") (pintype "passive"))
      (node (ref "U6") (pin "6") (pinfunction "OUT_6") (pintype "output"))
    )
    (net (code "130") (name "Net-(U8-+IN)") (class "Default")
      (node (ref "R54") (pin "2") (pinfunction "2_2") (pintype "passive"))
      (node (ref "U8") (pin "3") (pinfunction "+IN_3") (pintype "passive"))
    )
    (net (code "131") (name "Net-(U9-OUT)") (class "Default")
      (node (ref "R54") (pin "1") (pinfunction "1_1") (pintype "passive"))
      (node (ref "U9") (pin "6") (pinfunction "OUT_6") (pintype "output"))
    )
    (net (code "132") (name "unconnected-(DB1-MH1-Pad26)") (class "Default")
      (node (ref "DB1") (pin "26") (pinfunction "MH1_26") (pintype "passive"))
    )
    (net (code "133") (name "unconnected-(DB1-MH2-Pad27)") (class "Default")
      (node (ref "DB1") (pin "27") (pinfunction "MH2_27") (pintype "passive"))
    )
    (net (code "134") (name "unconnected-(DB1-Pad13)") (class "Default")
      (node (ref "DB1") (pin "13") (pinfunction "13_13") (pintype "passive+no_connect"))
    )
    (net (code "135") (name "unconnected-(K15-Pad4)") (class "Default")
      (node (ref "K15") (pin "4") (pinfunction "4_4") (pintype "passive+no_connect"))
    )
    (net (code "136") (name "unconnected-(K16-Pad4)") (class "Default")
      (node (ref "K16") (pin "4") (pinfunction "4_4") (pintype "passive"))
    )
    (net (code "137") (name "unconnected-(K17-Pad4)") (class "Default")
      (node (ref "K17") (pin "4") (pinfunction "4_4") (pintype "passive+no_connect"))
    )
    (net (code "138") (name "unconnected-(K18-Pad4)") (class "Default")
      (node (ref "K18") (pin "4") (pinfunction "4_4") (pintype "passive"))
    )
    (net (code "139") (name "unconnected-(K19-Pad4)") (class "Default")
      (node (ref "K19") (pin "4") (pinfunction "4_4") (pintype "passive+no_connect"))
    )
    (net (code "140") (name "unconnected-(K20-Pad4)") (class "Default")
      (node (ref "K20") (pin "4") (pinfunction "4_4") (pintype "passive+no_connect"))
    )
    (net (code "141") (name "unconnected-(K21-Pad4)") (class "Default")
      (node (ref "K21") (pin "4") (pinfunction "4_4") (pintype "passive+no_connect"))
    )
    (net (code "142") (name "unconnected-(RS1-No_Connect-Pad5)") (class "Default")
      (node (ref "RS1") (pin "5") (pinfunction "No_Connect_5") (pintype "passive"))
    )
    (net (code "143") (name "unconnected-(RS1-No_Connect-Pad6)") (class "Default")
      (node (ref "RS1") (pin "6") (pinfunction "No_Connect_6") (pintype "passive"))
    )
    (net (code "144") (name "unconnected-(RS2-No_Connect-Pad5)") (class "Default")
      (node (ref "RS2") (pin "5") (pinfunction "No_Connect_5") (pintype "passive"))
    )
    (net (code "145") (name "unconnected-(RS2-No_Connect-Pad6)") (class "Default")
      (node (ref "RS2") (pin "6") (pinfunction "No_Connect_6") (pintype "passive"))
    )
    (net (code "146") (name "unconnected-(RS3-No_Connect-Pad5)") (class "Default")
      (node (ref "RS3") (pin "5") (pinfunction "No_Connect_5") (pintype "passive"))
    )
    (net (code "147") (name "unconnected-(RS3-No_Connect-Pad6)") (class "Default")
      (node (ref "RS3") (pin "6") (pinfunction "No_Connect_6") (pintype "passive"))
    )
    (net (code "148") (name "unconnected-(TPS1-EN-Pad3)") (class "Default")
      (node (ref "TPS1") (pin "3") (pinfunction "EN_3") (pintype "passive+no_connect"))
    )
    (net (code "149") (name "unconnected-(U1-REF-Pad5)") (class "Default")
      (node (ref "U1") (pin "5") (pinfunction "REF_5") (pintype "input+no_connect"))
    )
    (net (code "150") (name "unconnected-(U1-RG-Pad1)") (class "Default")
      (node (ref "U1") (pin "1") (pinfunction "RG_1") (pintype "passive+no_connect"))
    )
    (net (code "151") (name "unconnected-(U1-RG-Pad8)") (class "Default")
      (node (ref "U1") (pin "8") (pinfunction "RG_8") (pintype "passive+no_connect"))
    )
    (net (code "152") (name "unconnected-(U2-REF-Pad5)") (class "Default")
      (node (ref "U2") (pin "5") (pinfunction "REF_5") (pintype "input+no_connect"))
    )
    (net (code "153") (name "unconnected-(U2-RG-Pad1)") (class "Default")
      (node (ref "U2") (pin "1") (pinfunction "RG_1") (pintype "passive+no_connect"))
    )
    (net (code "154") (name "unconnected-(U2-RG-Pad8)") (class "Default")
      (node (ref "U2") (pin "8") (pinfunction "RG_8") (pintype "passive+no_connect"))
    )
    (net (code "155") (name "unconnected-(U4-REF-Pad5)") (class "Default")
      (node (ref "U4") (pin "5") (pinfunction "REF_5") (pintype "input+no_connect"))
    )
    (net (code "156") (name "unconnected-(U4-RG-Pad1)") (class "Default")
      (node (ref "U4") (pin "1") (pinfunction "RG_1") (pintype "passive+no_connect"))
    )
    (net (code "157") (name "unconnected-(U4-RG-Pad8)") (class "Default")
      (node (ref "U4") (pin "8") (pinfunction "RG_8") (pintype "passive+no_connect"))
    )
    (net (code "158") (name "unconnected-(U5-REF-Pad5)") (class "Default")
      (node (ref "U5") (pin "5") (pinfunction "REF_5") (pintype "input+no_connect"))
    )
    (net (code "159") (name "unconnected-(U5-RG-Pad1)") (class "Default")
      (node (ref "U5") (pin "1") (pinfunction "RG_1") (pintype "passive+no_connect"))
    )
    (net (code "160") (name "unconnected-(U5-RG-Pad8)") (class "Default")
      (node (ref "U5") (pin "8") (pinfunction "RG_8") (pintype "passive+no_connect"))
    )
    (net (code "161") (name "unconnected-(U7-REF-Pad5)") (class "Default")
      (node (ref "U7") (pin "5") (pinfunction "REF_5") (pintype "input+no_connect"))
    )
    (net (code "162") (name "unconnected-(U7-RG-Pad1)") (class "Default")
      (node (ref "U7") (pin "1") (pinfunction "RG_1") (pintype "passive+no_connect"))
    )
    (net (code "163") (name "unconnected-(U7-RG-Pad8)") (class "Default")
      (node (ref "U7") (pin "8") (pinfunction "RG_8") (pintype "passive+no_connect"))
    )
    (net (code "164") (name "unconnected-(U8-REF-Pad5)") (class "Default")
      (node (ref "U8") (pin "5") (pinfunction "REF_5") (pintype "input+no_connect"))
    )
    (net (code "165") (name "unconnected-(U8-RG-Pad1)") (class "Default")
      (node (ref "U8") (pin "1") (pinfunction "RG_1") (pintype "passive+no_connect"))
    )
    (net (code "166") (name "unconnected-(U8-RG-Pad8)") (class "Default")
      (node (ref "U8") (pin "8") (pinfunction "RG_8") (pintype "passive+no_connect"))
    )
    (net (code "167") (name "unconnected-(UD1-IN7-Pad7)") (class "Default")
      (node (ref "UD1") (pin "7") (pinfunction "IN7_7") (pintype "input+no_connect"))
    )
    (net (code "168") (name "unconnected-(UD1-OT7-Pad10)") (class "Default")
      (node (ref "UD1") (pin "10") (pinfunction "OT7_10") (pintype "input+no_connect"))
    )
  )
)
